# Sij_Final.net
KiCad netlist of a schematic drawn in EAGLE
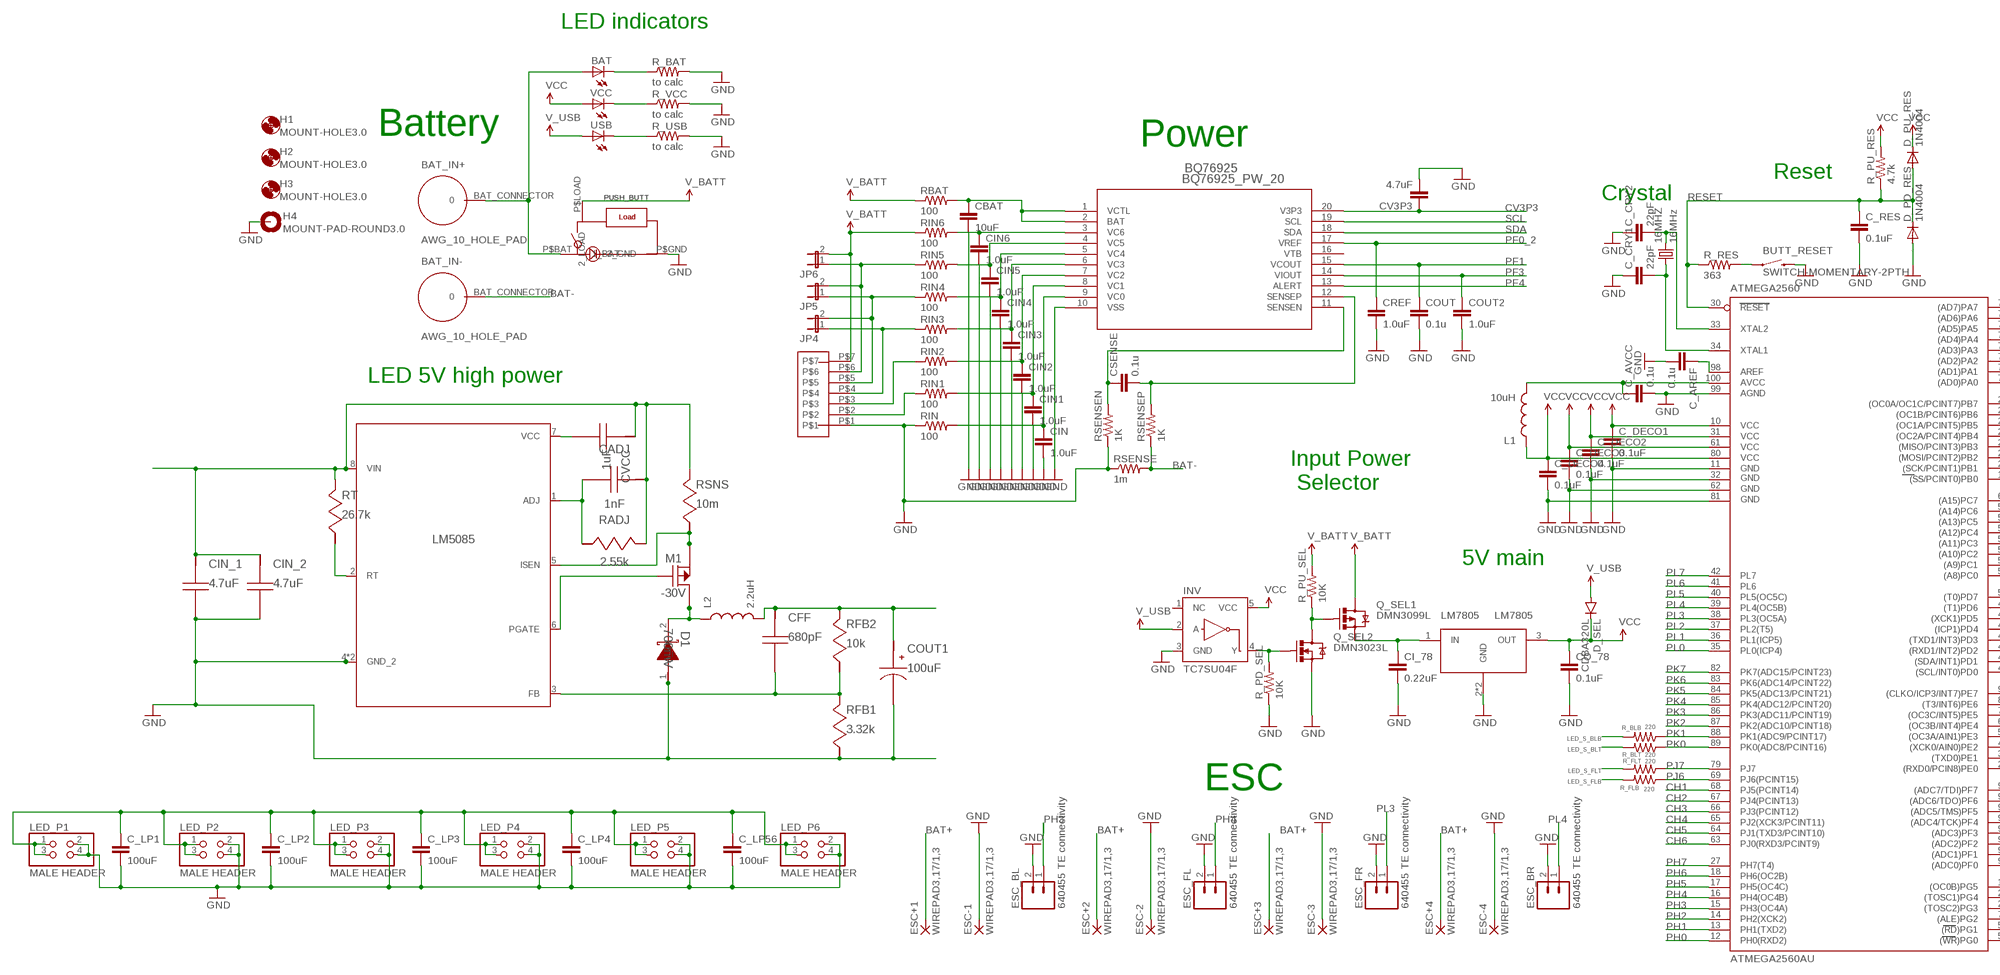
[diagram p0: schematic, sheet 1, part 1 of 2]
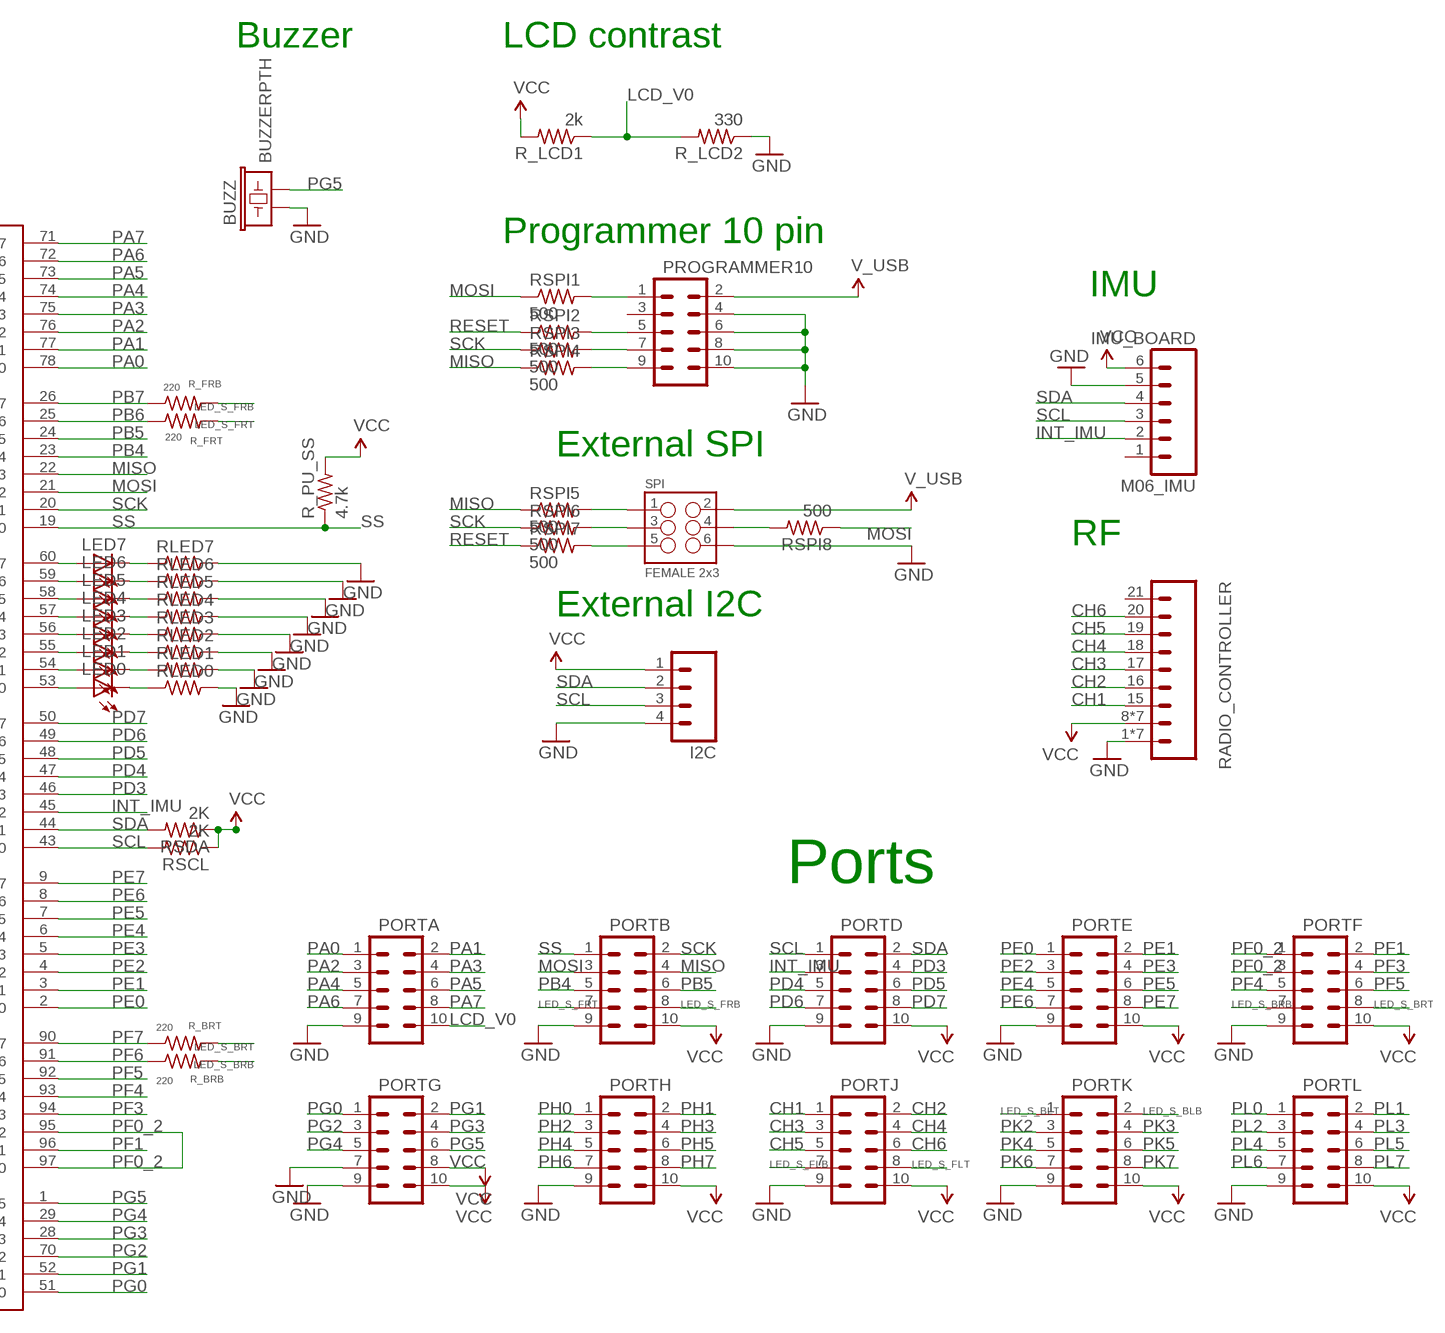
[diagram p1: schematic, sheet 1, part 2 of 2]

(export (version "E")
  (design (tool "Eeschema 10.0.6"))
  (components
    (comp (ref "16MHZ")
      (value "16MHz")
      (footprint "eagle-import:HC49US")
      (libsource (lib "eagle-import") (part "CRYSTALHC49US"))
    )
    (comp (ref "ATMEGA2560")
      (value "ATMEGA2560AU")
      (footprint "eagle-import:TQFP100")
      (libsource (lib "eagle-import") (part "ATMEGA2560AU"))
    )
    (comp (ref "BAT")
      (value "LEDCHIPLED_0805")
      (footprint "eagle-import:CHIPLED_0805")
      (libsource (lib "eagle-import") (part "LEDCHIPLED_0805"))
    )
    (comp (ref "BAT-MONIT")
      (value "7_PIN_JST-XH")
      (footprint "eagle-import:7_PIN_JST-XH")
      (libsource (lib "eagle-import") (part "7_PIN_JST-XH"))
    )
    (comp (ref "BAT_IN+")
      (value "AWG_10_HOLE_PAD")
      (footprint "eagle-import:AWG10_HOLE_PAD")
      (libsource (lib "eagle-import") (part "AWG_10_HOLE_PAD"))
    )
    (comp (ref "BAT_IN-")
      (value "AWG_10_HOLE_PAD")
      (footprint "eagle-import:AWG10_HOLE_PAD")
      (libsource (lib "eagle-import") (part "AWG_10_HOLE_PAD"))
    )
    (comp (ref "BQ76925")
      (value "BQ76925_PW_20")
      (footprint "eagle-import:PW20")
      (fields
        (field (name "GENERIC_PART_NUMBER") "BQ76925")
        (field (name "MANUFACTURER") "Texas Instruments")
        (field (name "MANUFACTURER_PART_NUMBER") "bq76925_pw_20")
      )
      (libsource (lib "eagle-import") (part "BQ76925_PW_20"))
    )
    (comp (ref "BUTT_RESET")
      (value "SWITCH-MOMENTARY-2PTH")
      (footprint "eagle-import:TACTILE-PTH")
      (libsource (lib "eagle-import") (part "SWITCH-MOMENTARY-2PTH"))
    )
    (comp (ref "BUZZ")
      (value "BUZZERPTH")
      (footprint "eagle-import:BUZZER-12MM")
      (libsource (lib "eagle-import") (part "BUZZERPTH"))
    )
    (comp (ref "CADJ")
      (value "1nF")
      (footprint "eagle-import:0201")
      (fields (field (name "MANUFACTURER_PART_NUMBER") "GRM033R71C102KA01D"))
      (libsource (lib "eagle-import") (part "GRM033R71C102KA01D"))
    )
    (comp (ref "CBAT")
      (value "10uF")
      (footprint "eagle-import:0805")
      (libsource (lib "eagle-import") (part "CAP0805"))
    )
    (comp (ref "CFF")
      (value "680pF")
      (footprint "eagle-import:0603")
      (fields (field (name "MANUFACTURER_PART_NUMBER") "GRM188R72E681KW07D"))
      (libsource (lib "eagle-import") (part "GRM188R72E681KW07D"))
    )
    (comp (ref "CIN")
      (value "1.0uF")
      (footprint "eagle-import:0603-CAP")
      (libsource (lib "eagle-import") (part "1.0UF-16V-10%(0603)"))
    )
    (comp (ref "CIN1")
      (value "1.0uF")
      (footprint "eagle-import:0603-CAP")
      (libsource (lib "eagle-import") (part "1.0UF-16V-10%(0603)"))
    )
    (comp (ref "CIN2")
      (value "1.0uF")
      (footprint "eagle-import:0603-CAP")
      (libsource (lib "eagle-import") (part "1.0UF-16V-10%(0603)"))
    )
    (comp (ref "CIN3")
      (value "1.0uF")
      (footprint "eagle-import:0603-CAP")
      (libsource (lib "eagle-import") (part "1.0UF-16V-10%(0603)"))
    )
    (comp (ref "CIN4")
      (value "1.0uF")
      (footprint "eagle-import:0603-CAP")
      (libsource (lib "eagle-import") (part "1.0UF-16V-10%(0603)"))
    )
    (comp (ref "CIN5")
      (value "1.0uF")
      (footprint "eagle-import:0603-CAP")
      (libsource (lib "eagle-import") (part "1.0UF-16V-10%(0603)"))
    )
    (comp (ref "CIN6")
      (value "1.0uF")
      (footprint "eagle-import:0603-CAP")
      (libsource (lib "eagle-import") (part "1.0UF-16V-10%(0603)"))
    )
    (comp (ref "CIN_1")
      (value "4.7uF")
      (footprint "eagle-import:0805")
      (fields (field (name "MANUFACTURER_PART_NUMBER") "GRM21BR61E475MA12L"))
      (libsource (lib "eagle-import") (part "GRM21BR61E475MA12L"))
    )
    (comp (ref "CIN_2")
      (value "4.7uF")
      (footprint "eagle-import:0805")
      (fields (field (name "MANUFACTURER_PART_NUMBER") "GRM21BR61E475MA12L"))
      (libsource (lib "eagle-import") (part "GRM21BR61E475MA12L"))
    )
    (comp (ref "CI_78")
      (value "0.22uF")
      (footprint "eagle-import:0603-CAP")
      (libsource (lib "eagle-import") (part "0.22UF-25V-10%(0603)"))
    )
    (comp (ref "COUT")
      (value "0.1u")
      (footprint "eagle-import:0603-CAP")
      (libsource (lib "eagle-import") (part "CAP0603-CAP"))
    )
    (comp (ref "COUT1")
      (value "100uF")
      (footprint "eagle-import:CAPSMT_6_A09")
      (fields (field (name "MANUFACTURER_PART_NUMBER") "6TPH100MAEA"))
      (libsource (lib "eagle-import") (part "6TPH100MAEA"))
    )
    (comp (ref "COUT2")
      (value "1.0uF")
      (footprint "eagle-import:0603-CAP")
      (libsource (lib "eagle-import") (part "1.0UF-16V-10%(0603)"))
    )
    (comp (ref "CO_78")
      (value "0.1uF")
      (footprint "eagle-import:0603-CAP")
      (libsource (lib "eagle-import") (part "0.1UF-25V-5%(0603)"))
    )
    (comp (ref "CREF")
      (value "1.0uF")
      (footprint "eagle-import:0603-CAP")
      (libsource (lib "eagle-import") (part "1.0UF-16V-10%(0603)"))
    )
    (comp (ref "CSENSE")
      (value "0.1u")
      (footprint "eagle-import:0603-CAP")
      (libsource (lib "eagle-import") (part "SparkFun-Passives_CAP0603-CAP"))
    )
    (comp (ref "CV3P3")
      (value "4.7uF")
      (footprint "eagle-import:0603-CAP")
      (libsource (lib "eagle-import") (part "4.7UF-6.3V-10%(0603)0603"))
    )
    (comp (ref "CVCC")
      (value "1uF")
      (footprint "eagle-import:0603")
      (fields (field (name "MANUFACTURER_PART_NUMBER") "GRM188R61C105KA93D"))
      (libsource (lib "eagle-import") (part "GRM188R61C105KA93D"))
    )
    (comp (ref "C_AREF")
      (value "0.1u")
      (footprint "eagle-import:0603-CAP")
      (libsource (lib "eagle-import") (part "CAP0603-CAP"))
    )
    (comp (ref "C_AVCC")
      (value "0.1u")
      (footprint "eagle-import:0603-CAP")
      (libsource (lib "eagle-import") (part "CAP0603-CAP"))
    )
    (comp (ref "C_CRY1")
      (value "22pF")
      (footprint "eagle-import:0603-CAP")
      (libsource (lib "eagle-import") (part "22PF-50V-5%(0603)"))
    )
    (comp (ref "C_CRY2")
      (value "22pF")
      (footprint "eagle-import:0603-CAP")
      (libsource (lib "eagle-import") (part "22PF-50V-5%(0603)"))
    )
    (comp (ref "C_DECO1")
      (value "0.1uF")
      (footprint "eagle-import:0603-CAP")
      (libsource (lib "eagle-import") (part "0.1UF-25V-5%(0603)"))
    )
    (comp (ref "C_DECO2")
      (value "0.1uF")
      (footprint "eagle-import:0603-CAP")
      (libsource (lib "eagle-import") (part "0.1UF-25V-5%(0603)"))
    )
    (comp (ref "C_DECO3")
      (value "0.1uF")
      (footprint "eagle-import:0603-CAP")
      (libsource (lib "eagle-import") (part "0.1UF-25V-5%(0603)"))
    )
    (comp (ref "C_DECO4")
      (value "0.1uF")
      (footprint "eagle-import:0603-CAP")
      (libsource (lib "eagle-import") (part "0.1UF-25V-5%(0603)"))
    )
    (comp (ref "C_LP1")
      (value "100uF")
      (footprint "eagle-import:1206")
      (libsource (lib "eagle-import") (part "CAP1206"))
    )
    (comp (ref "C_LP2")
      (value "100uF")
      (footprint "eagle-import:1206")
      (libsource (lib "eagle-import") (part "CAP1206"))
    )
    (comp (ref "C_LP3")
      (value "100uF")
      (footprint "eagle-import:1206")
      (libsource (lib "eagle-import") (part "CAP1206"))
    )
    (comp (ref "C_LP4")
      (value "100uF")
      (footprint "eagle-import:1206")
      (libsource (lib "eagle-import") (part "CAP1206"))
    )
    (comp (ref "C_LP56")
      (value "100uF")
      (footprint "eagle-import:1206")
      (libsource (lib "eagle-import") (part "CAP1206"))
    )
    (comp (ref "C_RES")
      (value "0.1uF")
      (footprint "eagle-import:0603-CAP")
      (libsource (lib "eagle-import") (part "0.1UF-25V-5%(0603)"))
    )
    (comp (ref "D1")
      (value "700mV")
      (footprint "eagle-import:DDPAK")
      (fields (field (name "MANUFACTURER_PART_NUMBER") "MBRB745PBF"))
      (libsource (lib "eagle-import") (part "MBRB745PBF"))
    )
    (comp (ref "D_PD_RES")
      (value "1N4004")
      (footprint "eagle-import:DO41-10")
      (libsource (lib "eagle-import") (part "1N4004"))
    )
    (comp (ref "D_PU_RES")
      (value "1N4004")
      (footprint "eagle-import:DO41-10")
      (libsource (lib "eagle-import") (part "1N4004"))
    )
    (comp (ref "D_SEL")
      (value "CDBA320L")
      (footprint "eagle-import:SMA-DIODE_ALT")
      (libsource (lib "eagle-import") (part "DIODESMA-ALT"))
    )
    (comp (ref "ESC+1")
      (value "WIREPAD3,17/1,3")
      (footprint "eagle-import:3,17_1,3")
      (libsource (lib "eagle-import") (part "WIREPAD3,17/1,3"))
    )
    (comp (ref "ESC+2")
      (value "WIREPAD3,17/1,3")
      (footprint "eagle-import:3,17_1,3")
      (libsource (lib "eagle-import") (part "WIREPAD3,17/1,3"))
    )
    (comp (ref "ESC+3")
      (value "WIREPAD3,17/1,3")
      (footprint "eagle-import:3,17_1,3")
      (libsource (lib "eagle-import") (part "WIREPAD3,17/1,3"))
    )
    (comp (ref "ESC+4")
      (value "WIREPAD3,17/1,3")
      (footprint "eagle-import:3,17_1,3")
      (libsource (lib "eagle-import") (part "WIREPAD3,17/1,3"))
    )
    (comp (ref "ESC-1")
      (value "WIREPAD3,17/1,3")
      (footprint "eagle-import:3,17_1,3")
      (libsource (lib "eagle-import") (part "WIREPAD3,17/1,3"))
    )
    (comp (ref "ESC-2")
      (value "WIREPAD3,17/1,3")
      (footprint "eagle-import:3,17_1,3")
      (libsource (lib "eagle-import") (part "WIREPAD3,17/1,3"))
    )
    (comp (ref "ESC-3")
      (value "WIREPAD3,17/1,3")
      (footprint "eagle-import:3,17_1,3")
      (libsource (lib "eagle-import") (part "WIREPAD3,17/1,3"))
    )
    (comp (ref "ESC-4")
      (value "WIREPAD3,17/1,3")
      (footprint "eagle-import:3,17_1,3")
      (libsource (lib "eagle-import") (part "WIREPAD3,17/1,3"))
    )
    (comp (ref "ESC_BL")
      (value "640455 TE connectivity")
      (footprint "eagle-import:1X02")
      (libsource (lib "eagle-import") (part "M02PTH"))
    )
    (comp (ref "ESC_BR")
      (value "640455 TE connectivity")
      (footprint "eagle-import:1X02")
      (libsource (lib "eagle-import") (part "M02PTH"))
    )
    (comp (ref "ESC_FL")
      (value "640455 TE connectivity")
      (footprint "eagle-import:1X02")
      (libsource (lib "eagle-import") (part "M02PTH"))
    )
    (comp (ref "ESC_FR")
      (value "640455 TE connectivity")
      (footprint "eagle-import:1X02")
      (libsource (lib "eagle-import") (part "M02PTH"))
    )
    (comp (ref "H1")
      (value "MOUNT-HOLE3.0")
      (footprint "eagle-import:3,0")
      (libsource (lib "eagle-import") (part "MOUNT-HOLE3.0"))
    )
    (comp (ref "H2")
      (value "MOUNT-HOLE3.0")
      (footprint "eagle-import:3,0")
      (libsource (lib "eagle-import") (part "MOUNT-HOLE3.0"))
    )
    (comp (ref "H3")
      (value "MOUNT-HOLE3.0")
      (footprint "eagle-import:3,0")
      (libsource (lib "eagle-import") (part "MOUNT-HOLE3.0"))
    )
    (comp (ref "H4")
      (value "MOUNT-PAD-ROUND3.0")
      (footprint "eagle-import:3,0-PAD")
      (libsource (lib "eagle-import") (part "MOUNT-PAD-ROUND3.0"))
    )
    (comp (ref "I2C")
      (value "M041X04_NO_SILK")
      (footprint "eagle-import:1X04_NO_SILK")
      (libsource (lib "eagle-import") (part "M041X04_NO_SILK"))
    )
    (comp (ref "IMU_BOARD")
      (value "M06_IMU")
      (footprint "eagle-import:1X06_LONGPADS")
      (libsource (lib "eagle-import") (part "M06_IMU"))
    )
    (comp (ref "INV")
      (value "TC7SU04F")
      (footprint "eagle-import:SOT23-5")
      (libsource (lib "eagle-import") (part "INVERTER_SOT23-5"))
    )
    (comp (ref "JP4")
      (value "JUMPER-2PTH")
      (footprint "eagle-import:1X02")
      (libsource (lib "eagle-import") (part "JUMPER-2PTH"))
    )
    (comp (ref "JP5")
      (value "JUMPER-2PTH")
      (footprint "eagle-import:1X02")
      (libsource (lib "eagle-import") (part "JUMPER-2PTH"))
    )
    (comp (ref "JP6")
      (value "JUMPER-2PTH")
      (footprint "eagle-import:1X02")
      (libsource (lib "eagle-import") (part "JUMPER-2PTH"))
    )
    (comp (ref "L1")
      (value "10uH")
      (footprint "eagle-import:0805")
      (libsource (lib "eagle-import") (part "INDUCTOR0805"))
    )
    (comp (ref "L2")
      (value "2.2uH")
      (footprint "eagle-import:MGV0605")
      (libsource (lib "eagle-import") (part "IND_MGV0605"))
    )
    (comp (ref "LED0")
      (value "LEDCHIPLED_0805")
      (footprint "eagle-import:CHIPLED_0805")
      (libsource (lib "eagle-import") (part "LEDCHIPLED_0805"))
    )
    (comp (ref "LED1")
      (value "LEDCHIPLED_0805")
      (footprint "eagle-import:CHIPLED_0805")
      (libsource (lib "eagle-import") (part "LEDCHIPLED_0805"))
    )
    (comp (ref "LED2")
      (value "LEDCHIPLED_0805")
      (footprint "eagle-import:CHIPLED_0805")
      (libsource (lib "eagle-import") (part "LEDCHIPLED_0805"))
    )
    (comp (ref "LED3")
      (value "LEDCHIPLED_0805")
      (footprint "eagle-import:CHIPLED_0805")
      (libsource (lib "eagle-import") (part "LEDCHIPLED_0805"))
    )
    (comp (ref "LED4")
      (value "LEDCHIPLED_0805")
      (footprint "eagle-import:CHIPLED_0805")
      (libsource (lib "eagle-import") (part "LEDCHIPLED_0805"))
    )
    (comp (ref "LED5")
      (value "LEDCHIPLED_0805")
      (footprint "eagle-import:CHIPLED_0805")
      (libsource (lib "eagle-import") (part "LEDCHIPLED_0805"))
    )
    (comp (ref "LED6")
      (value "LEDCHIPLED_0805")
      (footprint "eagle-import:CHIPLED_0805")
      (libsource (lib "eagle-import") (part "LEDCHIPLED_0805"))
    )
    (comp (ref "LED7")
      (value "LEDCHIPLED_0805")
      (footprint "eagle-import:CHIPLED_0805")
      (libsource (lib "eagle-import") (part "LEDCHIPLED_0805"))
    )
    (comp (ref "LED_P1")
      (value "MALE HEADER")
      (footprint "eagle-import:2X02")
      (libsource (lib "eagle-import") (part "PINHD-2X2"))
    )
    (comp (ref "LED_P2")
      (value "MALE HEADER")
      (footprint "eagle-import:2X02")
      (libsource (lib "eagle-import") (part "PINHD-2X2"))
    )
    (comp (ref "LED_P3")
      (value "MALE HEADER")
      (footprint "eagle-import:2X02")
      (libsource (lib "eagle-import") (part "PINHD-2X2"))
    )
    (comp (ref "LED_P4")
      (value "MALE HEADER")
      (footprint "eagle-import:2X02")
      (libsource (lib "eagle-import") (part "PINHD-2X2"))
    )
    (comp (ref "LED_P5")
      (value "MALE HEADER")
      (footprint "eagle-import:2X02")
      (libsource (lib "eagle-import") (part "PINHD-2X2"))
    )
    (comp (ref "LED_P6")
      (value "MALE HEADER")
      (footprint "eagle-import:2X02")
      (libsource (lib "eagle-import") (part "PINHD-2X2"))
    )
    (comp (ref "LM5085")
      (value "LM5085MY/NOPB")
      (footprint "eagle-import:MUY08A")
      (libsource (lib "eagle-import") (part "LM5085MY/NOPB"))
    )
    (comp (ref "LM7805")
      (value "LM7805")
      (footprint "eagle-import:KTT3")
      (libsource (lib "eagle-import") (part "LM7805"))
    )
    (comp (ref "M1")
      (value "-30V")
      (footprint "eagle-import:POWERPAK_SO-8")
      (fields (field (name "MANUFACTURER_PART_NUMBER") "Si7149DP"))
      (libsource (lib "eagle-import") (part "SI7149DP"))
    )
    (comp (ref "PORTA")
      (value "M05X2PTH")
      (footprint "eagle-import:AVR_ICSP")
      (libsource (lib "eagle-import") (part "M05X2PTH"))
    )
    (comp (ref "PORTB")
      (value "M05X2PTH")
      (footprint "eagle-import:AVR_ICSP")
      (libsource (lib "eagle-import") (part "M05X2PTH"))
    )
    (comp (ref "PORTD")
      (value "M05X2PTH")
      (footprint "eagle-import:AVR_ICSP")
      (libsource (lib "eagle-import") (part "M05X2PTH"))
    )
    (comp (ref "PORTE")
      (value "M05X2PTH")
      (footprint "eagle-import:AVR_ICSP")
      (libsource (lib "eagle-import") (part "M05X2PTH"))
    )
    (comp (ref "PORTF")
      (value "M05X2PTH")
      (footprint "eagle-import:AVR_ICSP")
      (libsource (lib "eagle-import") (part "M05X2PTH"))
    )
    (comp (ref "PORTG")
      (value "M05X2PTH")
      (footprint "eagle-import:AVR_ICSP")
      (libsource (lib "eagle-import") (part "M05X2PTH"))
    )
    (comp (ref "PORTH")
      (value "M05X2PTH")
      (footprint "eagle-import:AVR_ICSP")
      (libsource (lib "eagle-import") (part "M05X2PTH"))
    )
    (comp (ref "PORTJ")
      (value "M05X2PTH")
      (footprint "eagle-import:AVR_ICSP")
      (libsource (lib "eagle-import") (part "M05X2PTH"))
    )
    (comp (ref "PORTK")
      (value "M05X2PTH")
      (footprint "eagle-import:AVR_ICSP")
      (libsource (lib "eagle-import") (part "M05X2PTH"))
    )
    (comp (ref "PORTL")
      (value "M05X2PTH")
      (footprint "eagle-import:AVR_ICSP")
      (libsource (lib "eagle-import") (part "M05X2PTH"))
    )
    (comp (ref "PROGRAMMER10")
      (value "M05X2PTH")
      (footprint "eagle-import:AVR_ICSP")
      (libsource (lib "eagle-import") (part "M05X2PTH"))
    )
    (comp (ref "PUSH_BUTT")
      (value "PUSH_BUTTON")
      (footprint "eagle-import:PUSH_BUTTON")
      (libsource (lib "eagle-import") (part "PUSH_BUTTON"))
    )
    (comp (ref "Q_SEL1")
      (value "DMN3099L")
      (footprint "eagle-import:SOT23-3")
      (libsource (lib "eagle-import") (part "MOSFET-PCHANNEL"))
    )
    (comp (ref "Q_SEL2")
      (value "DMN3023L")
      (footprint "eagle-import:SOT23-3")
      (libsource (lib "eagle-import") (part "MOSFET-NCHANNELAO3404A"))
    )
    (comp (ref "RADIO_CONTROLLER")
      (value "RF_CONTROL_3X7_CON")
      (footprint "eagle-import:3X07")
      (libsource (lib "eagle-import") (part "RF_CONTROL_3X7_CON"))
    )
    (comp (ref "RADJ")
      (value "2.55k")
      (footprint "eagle-import:0603")
      (libsource (lib "eagle-import") (part "CRCW04022K55FKED"))
    )
    (comp (ref "RBAT")
      (value "100")
      (footprint "eagle-import:R0603")
      (libsource (lib "eagle-import") (part "R-US_R0603"))
    )
    (comp (ref "RFB1")
      (value "3.32k")
      (footprint "eagle-import:0603")
      (libsource (lib "eagle-import") (part "CRCW04023K32FKED"))
    )
    (comp (ref "RFB2")
      (value "10k")
      (footprint "eagle-import:0603")
      (libsource (lib "eagle-import") (part "CRCW040210K0FKED"))
    )
    (comp (ref "RIN")
      (value "100")
      (footprint "eagle-import:R0603")
      (libsource (lib "eagle-import") (part "R-US_R0603"))
    )
    (comp (ref "RIN1")
      (value "100")
      (footprint "eagle-import:R0603")
      (libsource (lib "eagle-import") (part "R-US_R0603"))
    )
    (comp (ref "RIN2")
      (value "100")
      (footprint "eagle-import:R0603")
      (libsource (lib "eagle-import") (part "R-US_R0603"))
    )
    (comp (ref "RIN3")
      (value "100")
      (footprint "eagle-import:R0603")
      (libsource (lib "eagle-import") (part "R-US_R0603"))
    )
    (comp (ref "RIN4")
      (value "100")
      (footprint "eagle-import:R0603")
      (libsource (lib "eagle-import") (part "R-US_R0603"))
    )
    (comp (ref "RIN5")
      (value "100")
      (footprint "eagle-import:R0603")
      (libsource (lib "eagle-import") (part "R-US_R0603"))
    )
    (comp (ref "RIN6")
      (value "100")
      (footprint "eagle-import:R0603")
      (libsource (lib "eagle-import") (part "R-US_R0603"))
    )
    (comp (ref "RLED0")
      (value "R-US_R0603")
      (footprint "eagle-import:R0603")
      (libsource (lib "eagle-import") (part "R-US_R0603"))
    )
    (comp (ref "RLED1")
      (value "R-US_R0603")
      (footprint "eagle-import:R0603")
      (libsource (lib "eagle-import") (part "R-US_R0603"))
    )
    (comp (ref "RLED2")
      (value "R-US_R0603")
      (footprint "eagle-import:R0603")
      (libsource (lib "eagle-import") (part "R-US_R0603"))
    )
    (comp (ref "RLED3")
      (value "R-US_R0603")
      (footprint "eagle-import:R0603")
      (libsource (lib "eagle-import") (part "R-US_R0603"))
    )
    (comp (ref "RLED4")
      (value "R-US_R0603")
      (footprint "eagle-import:R0603")
      (libsource (lib "eagle-import") (part "R-US_R0603"))
    )
    (comp (ref "RLED5")
      (value "R-US_R0603")
      (footprint "eagle-import:R0603")
      (libsource (lib "eagle-import") (part "R-US_R0603"))
    )
    (comp (ref "RLED6")
      (value "R-US_R0603")
      (footprint "eagle-import:R0603")
      (libsource (lib "eagle-import") (part "R-US_R0603"))
    )
    (comp (ref "RLED7")
      (value "R-US_R0603")
      (footprint "eagle-import:R0603")
      (libsource (lib "eagle-import") (part "R-US_R0603"))
    )
    (comp (ref "RSCL")
      (value "2K")
      (footprint "eagle-import:R0603")
      (libsource (lib "eagle-import") (part "R-US_R0603"))
    )
    (comp (ref "RSDA")
      (value "2K")
      (footprint "eagle-import:R0603")
      (libsource (lib "eagle-import") (part "R-US_R0603"))
    )
    (comp (ref "RSENSE")
      (value "1m")
      (footprint "eagle-import:R1206")
      (libsource (lib "eagle-import") (part "R-US_R1206"))
    )
    (comp (ref "RSENSEN")
      (value "1K")
      (footprint "eagle-import:R0603")
      (libsource (lib "eagle-import") (part "R-US_R0603"))
    )
    (comp (ref "RSENSEP")
      (value "1K")
      (footprint "eagle-import:R0603")
      (libsource (lib "eagle-import") (part "R-US_R0603"))
    )
    (comp (ref "RSNS")
      (value "10m")
      (footprint "eagle-import:1206")
      (fields
        (field (name "MANUFACTURER_PART_NUMBER") "CSR1206FK10L0")
        (field (name "POWER") "0.5")
        (field (name "TOLERANCE") "1.0")
      )
      (libsource (lib "eagle-import") (part "CSR1206FK10L0"))
    )
    (comp (ref "RSPI1")
      (value "500")
      (footprint "eagle-import:R0603")
      (libsource (lib "eagle-import") (part "R-US_R0603"))
    )
    (comp (ref "RSPI2")
      (value "500")
      (footprint "eagle-import:R0603")
      (libsource (lib "eagle-import") (part "R-US_R0603"))
    )
    (comp (ref "RSPI3")
      (value "500")
      (footprint "eagle-import:R0603")
      (libsource (lib "eagle-import") (part "R-US_R0603"))
    )
    (comp (ref "RSPI4")
      (value "500")
      (footprint "eagle-import:R0603")
      (libsource (lib "eagle-import") (part "R-US_R0603"))
    )
    (comp (ref "RSPI5")
      (value "500")
      (footprint "eagle-import:R0603")
      (libsource (lib "eagle-import") (part "R-US_R0603"))
    )
    (comp (ref "RSPI6")
      (value "500")
      (footprint "eagle-import:R0603")
      (libsource (lib "eagle-import") (part "R-US_R0603"))
    )
    (comp (ref "RSPI7")
      (value "500")
      (footprint "eagle-import:R0603")
      (libsource (lib "eagle-import") (part "R-US_R0603"))
    )
    (comp (ref "RSPI8")
      (value "500")
      (footprint "eagle-import:R0603")
      (libsource (lib "eagle-import") (part "R-US_R0603"))
    )
    (comp (ref "RT")
      (value "26.7k")
      (footprint "eagle-import:0603")
      (libsource (lib "eagle-import") (part "CRCW040226K7FKED"))
    )
    (comp (ref "R_BAT")
      (value "to calc")
      (footprint "eagle-import:R0603")
      (libsource (lib "eagle-import") (part "R-US_R0603"))
    )
    (comp (ref "R_BLB")
      (value "220")
      (footprint "eagle-import:R0603")
      (libsource (lib "eagle-import") (part "R-US_R0603"))
    )
    (comp (ref "R_BLT")
      (value "220")
      (footprint "eagle-import:R0603")
      (libsource (lib "eagle-import") (part "R-US_R0603"))
    )
    (comp (ref "R_BRB")
      (value "220")
      (footprint "eagle-import:R0603")
      (libsource (lib "eagle-import") (part "R-US_R0603"))
    )
    (comp (ref "R_BRT")
      (value "220")
      (footprint "eagle-import:R0603")
      (libsource (lib "eagle-import") (part "R-US_R0603"))
    )
    (comp (ref "R_FLB")
      (value "220")
      (footprint "eagle-import:R0603")
      (libsource (lib "eagle-import") (part "R-US_R0603"))
    )
    (comp (ref "R_FLT")
      (value "220")
      (footprint "eagle-import:R0603")
      (libsource (lib "eagle-import") (part "R-US_R0603"))
    )
    (comp (ref "R_FRB")
      (value "220")
      (footprint "eagle-import:R0603")
      (libsource (lib "eagle-import") (part "R-US_R0603"))
    )
    (comp (ref "R_FRT")
      (value "220")
      (footprint "eagle-import:R0603")
      (libsource (lib "eagle-import") (part "R-US_R0603"))
    )
    (comp (ref "R_LCD1")
      (value "2k")
      (footprint "eagle-import:R0603")
      (libsource (lib "eagle-import") (part "R-US_R0603"))
    )
    (comp (ref "R_LCD2")
      (value "330")
      (footprint "eagle-import:R0603")
      (libsource (lib "eagle-import") (part "R-US_R0603"))
    )
    (comp (ref "R_PD_SEL")
      (value "10K")
      (footprint "eagle-import:R0603")
      (libsource (lib "eagle-import") (part "R-US_R0603"))
    )
    (comp (ref "R_PU_RES")
      (value "4.7k")
      (footprint "eagle-import:R0603")
      (libsource (lib "eagle-import") (part "R-US_R0603"))
    )
    (comp (ref "R_PU_SEL")
      (value "10K")
      (footprint "eagle-import:R0603")
      (libsource (lib "eagle-import") (part "R-US_R0603"))
    )
    (comp (ref "R_PU_SS")
      (value "4.7k")
      (footprint "eagle-import:R0603")
      (libsource (lib "eagle-import") (part "R-US_R0603"))
    )
    (comp (ref "R_RES")
      (value "363")
      (footprint "eagle-import:R0603")
      (libsource (lib "eagle-import") (part "R-US_R0603"))
    )
    (comp (ref "R_USB")
      (value "to calc")
      (footprint "eagle-import:R0603")
      (libsource (lib "eagle-import") (part "R-US_R0603"))
    )
    (comp (ref "R_VCC")
      (value "to calc")
      (footprint "eagle-import:R0603")
      (libsource (lib "eagle-import") (part "R-US_R0603"))
    )
    (comp (ref "SPI")
      (value "FEMALE 2x3")
      (footprint "eagle-import:2X3")
      (libsource (lib "eagle-import") (part "M03X2FEMALE"))
    )
    (comp (ref "USB")
      (value "LEDCHIPLED_0805")
      (footprint "eagle-import:CHIPLED_0805")
      (libsource (lib "eagle-import") (part "LEDCHIPLED_0805"))
    )
    (comp (ref "VCC")
      (value "LEDCHIPLED_0805")
      (footprint "eagle-import:CHIPLED_0805")
      (libsource (lib "eagle-import") (part "LEDCHIPLED_0805"))
    )
  )
  (nets
    (net (code "1") (name "/BAT+") (class "Default")
      (node (ref "BAT") (pin "A") (pinfunction "A_A") (pintype "passive"))
      (node (ref "BAT_IN+") (pin "BAT_CONNECTOR") (pinfunction "0_BAT_CONNECTOR") (pintype "bidirectional"))
      (node (ref "ESC+1") (pin "1") (pinfunction "P_1") (pintype "passive"))
      (node (ref "ESC+2") (pin "1") (pinfunction "P_1") (pintype "passive"))
      (node (ref "ESC+3") (pin "1") (pinfunction "P_1") (pintype "passive"))
      (node (ref "ESC+4") (pin "1") (pinfunction "P_1") (pintype "passive"))
      (node (ref "PUSH_BUTT") (pin "P$BAT") (pinfunction "1_BAT_P$BAT") (pintype "bidirectional"))
    )
    (net (code "2") (name "/BAT-") (class "Default")
      (node (ref "BAT_IN-") (pin "BAT_CONNECTOR") (pinfunction "0_BAT_CONNECTOR") (pintype "bidirectional"))
      (node (ref "RSENSE") (pin "2") (pinfunction "2_2") (pintype "passive"))
      (node (ref "RSENSEP") (pin "1") (pinfunction "1_1") (pintype "passive"))
    )
    (net (code "3") (name "/CH1") (class "Default")
      (node (ref "ATMEGA2560") (pin "68") (pinfunction "PJ5(PCINT14)_68") (pintype "bidirectional"))
      (node (ref "PORTJ") (pin "1") (pinfunction "1_1") (pintype "passive"))
      (node (ref "RADIO_CONTROLLER") (pin "15") (pinfunction "1_15") (pintype "bidirectional"))
    )
    (net (code "4") (name "/CH2") (class "Default")
      (node (ref "ATMEGA2560") (pin "67") (pinfunction "PJ4(PCINT13)_67") (pintype "bidirectional"))
      (node (ref "PORTJ") (pin "2") (pinfunction "2_2") (pintype "passive"))
      (node (ref "RADIO_CONTROLLER") (pin "16") (pinfunction "2_16") (pintype "bidirectional"))
    )
    (net (code "5") (name "/CH3") (class "Default")
      (node (ref "ATMEGA2560") (pin "66") (pinfunction "PJ3(PCINT12)_66") (pintype "bidirectional"))
      (node (ref "PORTJ") (pin "3") (pinfunction "3_3") (pintype "passive"))
      (node (ref "RADIO_CONTROLLER") (pin "17") (pinfunction "3_17") (pintype "bidirectional"))
    )
    (net (code "6") (name "/CH4") (class "Default")
      (node (ref "ATMEGA2560") (pin "65") (pinfunction "PJ2(XCK3/PCINT11)_65") (pintype "bidirectional"))
      (node (ref "PORTJ") (pin "4") (pinfunction "4_4") (pintype "passive"))
      (node (ref "RADIO_CONTROLLER") (pin "18") (pinfunction "4_18") (pintype "bidirectional"))
    )
    (net (code "7") (name "/CH5") (class "Default")
      (node (ref "ATMEGA2560") (pin "64") (pinfunction "PJ1(TXD3/PCINT10)_64") (pintype "bidirectional"))
      (node (ref "PORTJ") (pin "5") (pinfunction "5_5") (pintype "passive"))
      (node (ref "RADIO_CONTROLLER") (pin "19") (pinfunction "5_19") (pintype "bidirectional"))
    )
    (net (code "8") (name "/CH6") (class "Default")
      (node (ref "ATMEGA2560") (pin "63") (pinfunction "PJ0(RXD3/PCINT9)_63") (pintype "bidirectional"))
      (node (ref "PORTJ") (pin "6") (pinfunction "6_6") (pintype "passive"))
      (node (ref "RADIO_CONTROLLER") (pin "20") (pinfunction "6_20") (pintype "bidirectional"))
    )
    (net (code "9") (name "/CV3P3") (class "Default")
      (node (ref "BQ76925") (pin "20") (pinfunction "V3P3_20") (pintype "output"))
      (node (ref "CV3P3") (pin "1") (pinfunction "1_1") (pintype "passive"))
    )
    (net (code "10") (name "/INT_IMU") (class "Default")
      (node (ref "ATMEGA2560") (pin "45") (pinfunction "(RXD1/INT2)PD2_45") (pintype "bidirectional"))
      (node (ref "IMU_BOARD") (pin "2") (pinfunction "2_2") (pintype "passive"))
      (node (ref "PORTD") (pin "3") (pinfunction "3_3") (pintype "passive"))
    )
    (net (code "11") (name "/LCD_V0") (class "Default")
      (node (ref "PORTA") (pin "10") (pinfunction "10_10") (pintype "passive"))
      (node (ref "R_LCD1") (pin "1") (pinfunction "1_1") (pintype "passive"))
      (node (ref "R_LCD2") (pin "2") (pinfunction "2_2") (pintype "passive"))
    )
    (net (code "12") (name "/LED_S_BLB") (class "Default")
      (node (ref "PORTK") (pin "2") (pinfunction "2_2") (pintype "passive"))
      (node (ref "R_BLB") (pin "2") (pinfunction "2_2") (pintype "passive"))
    )
    (net (code "13") (name "/LED_S_BLT") (class "Default")
      (node (ref "PORTK") (pin "1") (pinfunction "1_1") (pintype "passive"))
      (node (ref "R_BLT") (pin "2") (pinfunction "2_2") (pintype "passive"))
    )
    (net (code "14") (name "/LED_S_BRB") (class "Default")
      (node (ref "PORTF") (pin "7") (pinfunction "7_7") (pintype "passive"))
      (node (ref "R_BRB") (pin "2") (pinfunction "2_2") (pintype "passive"))
    )
    (net (code "15") (name "/LED_S_BRT") (class "Default")
      (node (ref "PORTF") (pin "8") (pinfunction "8_8") (pintype "passive"))
      (node (ref "R_BRT") (pin "2") (pinfunction "2_2") (pintype "passive"))
    )
    (net (code "16") (name "/LED_S_FLB") (class "Default")
      (node (ref "PORTJ") (pin "7") (pinfunction "7_7") (pintype "passive"))
      (node (ref "R_FLB") (pin "2") (pinfunction "2_2") (pintype "passive"))
    )
    (net (code "17") (name "/LED_S_FLT") (class "Default")
      (node (ref "PORTJ") (pin "8") (pinfunction "8_8") (pintype "passive"))
      (node (ref "R_FLT") (pin "2") (pinfunction "2_2") (pintype "passive"))
    )
    (net (code "18") (name "/LED_S_FRB") (class "Default")
      (node (ref "PORTB") (pin "8") (pinfunction "8_8") (pintype "passive"))
      (node (ref "R_FRB") (pin "2") (pinfunction "2_2") (pintype "passive"))
    )
    (net (code "19") (name "/LED_S_FRT") (class "Default")
      (node (ref "PORTB") (pin "7") (pinfunction "7_7") (pintype "passive"))
      (node (ref "R_FRT") (pin "2") (pinfunction "2_2") (pintype "passive"))
    )
    (net (code "20") (name "/MISO") (class "Default")
      (node (ref "ATMEGA2560") (pin "22") (pinfunction "(MISO/PCINT3)PB3_22") (pintype "bidirectional"))
      (node (ref "PORTB") (pin "4") (pinfunction "4_4") (pintype "passive"))
      (node (ref "RSPI4") (pin "1") (pinfunction "1_1") (pintype "passive"))
      (node (ref "RSPI5") (pin "1") (pinfunction "1_1") (pintype "passive"))
    )
    (net (code "21") (name "/MOSI") (class "Default")
      (node (ref "ATMEGA2560") (pin "21") (pinfunction "(MOSI/PCINT2)PB2_21") (pintype "bidirectional"))
      (node (ref "PORTB") (pin "3") (pinfunction "3_3") (pintype "passive"))
      (node (ref "RSPI1") (pin "1") (pinfunction "1_1") (pintype "passive"))
      (node (ref "RSPI8") (pin "1") (pinfunction "1_1") (pintype "passive"))
    )
    (net (code "22") (name "/PA0") (class "Default")
      (node (ref "ATMEGA2560") (pin "78") (pinfunction "(AD0)PA0_78") (pintype "bidirectional"))
      (node (ref "PORTA") (pin "1") (pinfunction "1_1") (pintype "passive"))
    )
    (net (code "23") (name "/PA1") (class "Default")
      (node (ref "ATMEGA2560") (pin "77") (pinfunction "(AD1)PA1_77") (pintype "bidirectional"))
      (node (ref "PORTA") (pin "2") (pinfunction "2_2") (pintype "passive"))
    )
    (net (code "24") (name "/PA2") (class "Default")
      (node (ref "ATMEGA2560") (pin "76") (pinfunction "(AD2)PA2_76") (pintype "bidirectional"))
      (node (ref "PORTA") (pin "3") (pinfunction "3_3") (pintype "passive"))
    )
    (net (code "25") (name "/PA3") (class "Default")
      (node (ref "ATMEGA2560") (pin "75") (pinfunction "(AD3)PA3_75") (pintype "bidirectional"))
      (node (ref "PORTA") (pin "4") (pinfunction "4_4") (pintype "passive"))
    )
    (net (code "26") (name "/PA4") (class "Default")
      (node (ref "ATMEGA2560") (pin "74") (pinfunction "(AD4)PA4_74") (pintype "bidirectional"))
      (node (ref "PORTA") (pin "5") (pinfunction "5_5") (pintype "passive"))
    )
    (net (code "27") (name "/PA5") (class "Default")
      (node (ref "ATMEGA2560") (pin "73") (pinfunction "(AD5)PA5_73") (pintype "bidirectional"))
      (node (ref "PORTA") (pin "6") (pinfunction "6_6") (pintype "passive"))
    )
    (net (code "28") (name "/PA6") (class "Default")
      (node (ref "ATMEGA2560") (pin "72") (pinfunction "(AD6)PA6_72") (pintype "bidirectional"))
      (node (ref "PORTA") (pin "7") (pinfunction "7_7") (pintype "passive"))
    )
    (net (code "29") (name "/PA7") (class "Default")
      (node (ref "ATMEGA2560") (pin "71") (pinfunction "(AD7)PA7_71") (pintype "bidirectional"))
      (node (ref "PORTA") (pin "8") (pinfunction "8_8") (pintype "passive"))
    )
    (net (code "30") (name "/PB4") (class "Default")
      (node (ref "ATMEGA2560") (pin "23") (pinfunction "(OC2A/PCINT4)PB4_23") (pintype "bidirectional"))
      (node (ref "PORTB") (pin "5") (pinfunction "5_5") (pintype "passive"))
    )
    (net (code "31") (name "/PB5") (class "Default")
      (node (ref "ATMEGA2560") (pin "24") (pinfunction "(OC1A/PCINT5)PB5_24") (pintype "bidirectional"))
      (node (ref "PORTB") (pin "6") (pinfunction "6_6") (pintype "passive"))
    )
    (net (code "32") (name "/PB6") (class "Default")
      (node (ref "ATMEGA2560") (pin "25") (pinfunction "(OC1B/PCINT6)PB6_25") (pintype "bidirectional"))
      (node (ref "R_FRT") (pin "1") (pinfunction "1_1") (pintype "passive"))
    )
    (net (code "33") (name "/PB7") (class "Default")
      (node (ref "ATMEGA2560") (pin "26") (pinfunction "(OC0A/OC1C/PCINT7)PB7_26") (pintype "bidirectional"))
      (node (ref "R_FRB") (pin "1") (pinfunction "1_1") (pintype "passive"))
    )
    (net (code "34") (name "/PD3") (class "Default")
      (node (ref "ATMEGA2560") (pin "46") (pinfunction "(TXD1/INT3)PD3_46") (pintype "bidirectional"))
      (node (ref "PORTD") (pin "4") (pinfunction "4_4") (pintype "passive"))
    )
    (net (code "35") (name "/PD4") (class "Default")
      (node (ref "ATMEGA2560") (pin "47") (pinfunction "(ICP1)PD4_47") (pintype "bidirectional"))
      (node (ref "PORTD") (pin "5") (pinfunction "5_5") (pintype "passive"))
    )
    (net (code "36") (name "/PD5") (class "Default")
      (node (ref "ATMEGA2560") (pin "48") (pinfunction "(XCK1)PD5_48") (pintype "bidirectional"))
      (node (ref "PORTD") (pin "6") (pinfunction "6_6") (pintype "passive"))
    )
    (net (code "37") (name "/PD6") (class "Default")
      (node (ref "ATMEGA2560") (pin "49") (pinfunction "(T1)PD6_49") (pintype "bidirectional"))
      (node (ref "PORTD") (pin "7") (pinfunction "7_7") (pintype "passive"))
    )
    (net (code "38") (name "/PD7") (class "Default")
      (node (ref "ATMEGA2560") (pin "50") (pinfunction "(T0)PD7_50") (pintype "bidirectional"))
      (node (ref "PORTD") (pin "8") (pinfunction "8_8") (pintype "passive"))
    )
    (net (code "39") (name "/PE0") (class "Default")
      (node (ref "ATMEGA2560") (pin "2") (pinfunction "(RXD0/PCIN8)PE0_2") (pintype "bidirectional"))
      (node (ref "PORTE") (pin "1") (pinfunction "1_1") (pintype "passive"))
    )
    (net (code "40") (name "/PE1") (class "Default")
      (node (ref "ATMEGA2560") (pin "3") (pinfunction "(TXD0)PE1_3") (pintype "bidirectional"))
      (node (ref "PORTE") (pin "2") (pinfunction "2_2") (pintype "passive"))
    )
    (net (code "41") (name "/PE2") (class "Default")
      (node (ref "ATMEGA2560") (pin "4") (pinfunction "(XCK0/AIN0)PE2_4") (pintype "bidirectional"))
      (node (ref "PORTE") (pin "3") (pinfunction "3_3") (pintype "passive"))
    )
    (net (code "42") (name "/PE3") (class "Default")
      (node (ref "ATMEGA2560") (pin "5") (pinfunction "(OC3A/AIN1)PE3_5") (pintype "bidirectional"))
      (node (ref "PORTE") (pin "4") (pinfunction "4_4") (pintype "passive"))
    )
    (net (code "43") (name "/PE4") (class "Default")
      (node (ref "ATMEGA2560") (pin "6") (pinfunction "(OC3B/INT4)PE4_6") (pintype "bidirectional"))
      (node (ref "PORTE") (pin "5") (pinfunction "5_5") (pintype "passive"))
    )
    (net (code "44") (name "/PE5") (class "Default")
      (node (ref "ATMEGA2560") (pin "7") (pinfunction "(OC3C/INT5)PE5_7") (pintype "bidirectional"))
      (node (ref "PORTE") (pin "6") (pinfunction "6_6") (pintype "passive"))
    )
    (net (code "45") (name "/PE6") (class "Default")
      (node (ref "ATMEGA2560") (pin "8") (pinfunction "(T3/INT6)PE6_8") (pintype "bidirectional"))
      (node (ref "PORTE") (pin "7") (pinfunction "7_7") (pintype "passive"))
    )
    (net (code "46") (name "/PE7") (class "Default")
      (node (ref "ATMEGA2560") (pin "9") (pinfunction "(CLKO/ICP3/INT7)PE7_9") (pintype "bidirectional"))
      (node (ref "PORTE") (pin "8") (pinfunction "8_8") (pintype "passive"))
    )
    (net (code "47") (name "/PF0_2") (class "Default")
      (node (ref "ATMEGA2560") (pin "95") (pinfunction "(ADC2)PF2_95") (pintype "bidirectional"))
      (node (ref "ATMEGA2560") (pin "97") (pinfunction "(ADC0)PF0_97") (pintype "bidirectional"))
      (node (ref "BQ76925") (pin "17") (pinfunction "VREF_17") (pintype "output"))
      (node (ref "CREF") (pin "1") (pinfunction "1_1") (pintype "passive"))
      (node (ref "PORTF") (pin "1") (pinfunction "1_1") (pintype "passive"))
      (node (ref "PORTF") (pin "3") (pinfunction "3_3") (pintype "passive"))
    )
    (net (code "48") (name "/PF1") (class "Default")
      (node (ref "ATMEGA2560") (pin "96") (pinfunction "(ADC1)PF1_96") (pintype "bidirectional"))
      (node (ref "BQ76925") (pin "15") (pinfunction "VCOUT_15") (pintype "output"))
      (node (ref "COUT") (pin "1") (pinfunction "1_1") (pintype "passive"))
      (node (ref "PORTF") (pin "2") (pinfunction "2_2") (pintype "passive"))
    )
    (net (code "49") (name "/PF3") (class "Default")
      (node (ref "ATMEGA2560") (pin "94") (pinfunction "(ADC3)PF3_94") (pintype "bidirectional"))
      (node (ref "BQ76925") (pin "14") (pinfunction "VIOUT_14") (pintype "output"))
      (node (ref "COUT2") (pin "1") (pinfunction "1_1") (pintype "passive"))
      (node (ref "PORTF") (pin "4") (pinfunction "4_4") (pintype "passive"))
    )
    (net (code "50") (name "/PF4") (class "Default")
      (node (ref "ATMEGA2560") (pin "93") (pinfunction "(ADC4/TCK)PF4_93") (pintype "bidirectional"))
      (node (ref "BQ76925") (pin "13") (pinfunction "ALERT_13") (pintype "output"))
      (node (ref "PORTF") (pin "5") (pinfunction "5_5") (pintype "passive"))
    )
    (net (code "51") (name "/PF5") (class "Default")
      (node (ref "ATMEGA2560") (pin "92") (pinfunction "(ADC5/TMS)PF5_92") (pintype "bidirectional"))
      (node (ref "PORTF") (pin "6") (pinfunction "6_6") (pintype "passive"))
    )
    (net (code "52") (name "/PF6") (class "Default")
      (node (ref "ATMEGA2560") (pin "91") (pinfunction "(ADC6/TDO)PF6_91") (pintype "bidirectional"))
      (node (ref "R_BRB") (pin "1") (pinfunction "1_1") (pintype "passive"))
    )
    (net (code "53") (name "/PF7") (class "Default")
      (node (ref "ATMEGA2560") (pin "90") (pinfunction "(ADC7/TDI)PF7_90") (pintype "bidirectional"))
      (node (ref "R_BRT") (pin "1") (pinfunction "1_1") (pintype "passive"))
    )
    (net (code "54") (name "/PG0") (class "Default")
      (node (ref "ATMEGA2560") (pin "51") (pinfunction "(WR)PG0_51") (pintype "bidirectional"))
      (node (ref "PORTG") (pin "1") (pinfunction "1_1") (pintype "passive"))
    )
    (net (code "55") (name "/PG1") (class "Default")
      (node (ref "ATMEGA2560") (pin "52") (pinfunction "(RD)PG1_52") (pintype "bidirectional"))
      (node (ref "PORTG") (pin "2") (pinfunction "2_2") (pintype "passive"))
    )
    (net (code "56") (name "/PG2") (class "Default")
      (node (ref "ATMEGA2560") (pin "70") (pinfunction "(ALE)PG2_70") (pintype "bidirectional"))
      (node (ref "PORTG") (pin "3") (pinfunction "3_3") (pintype "passive"))
    )
    (net (code "57") (name "/PG3") (class "Default")
      (node (ref "ATMEGA2560") (pin "28") (pinfunction "(TOSC2)PG3_28") (pintype "bidirectional"))
      (node (ref "PORTG") (pin "4") (pinfunction "4_4") (pintype "passive"))
    )
    (net (code "58") (name "/PG4") (class "Default")
      (node (ref "ATMEGA2560") (pin "29") (pinfunction "(TOSC1)PG4_29") (pintype "bidirectional"))
      (node (ref "PORTG") (pin "5") (pinfunction "5_5") (pintype "passive"))
    )
    (net (code "59") (name "/PG5") (class "Default")
      (node (ref "ATMEGA2560") (pin "1") (pinfunction "(OC0B)PG5_1") (pintype "bidirectional"))
      (node (ref "BUZZ") (pin "-") (pinfunction "2_-") (pintype "passive"))
      (node (ref "PORTG") (pin "6") (pinfunction "6_6") (pintype "passive"))
    )
    (net (code "60") (name "/PH0") (class "Default")
      (node (ref "ATMEGA2560") (pin "12") (pinfunction "PH0(RXD2)_12") (pintype "bidirectional"))
      (node (ref "PORTH") (pin "1") (pinfunction "1_1") (pintype "passive"))
    )
    (net (code "61") (name "/PH1") (class "Default")
      (node (ref "ATMEGA2560") (pin "13") (pinfunction "PH1(TXD2)_13") (pintype "bidirectional"))
      (node (ref "PORTH") (pin "2") (pinfunction "2_2") (pintype "passive"))
    )
    (net (code "62") (name "/PH2") (class "Default")
      (node (ref "ATMEGA2560") (pin "14") (pinfunction "PH2(XCK2)_14") (pintype "bidirectional"))
      (node (ref "PORTH") (pin "3") (pinfunction "3_3") (pintype "passive"))
    )
    (net (code "63") (name "/PH3") (class "Default")
      (node (ref "ATMEGA2560") (pin "15") (pinfunction "PH3(OC4A)_15") (pintype "bidirectional"))
      (node (ref "ESC_BL") (pin "1") (pinfunction "1_1") (pintype "passive"))
      (node (ref "PORTH") (pin "4") (pinfunction "4_4") (pintype "passive"))
    )
    (net (code "64") (name "/PH4") (class "Default")
      (node (ref "ATMEGA2560") (pin "16") (pinfunction "PH4(OC4B)_16") (pintype "bidirectional"))
      (node (ref "ESC_FL") (pin "1") (pinfunction "1_1") (pintype "passive"))
      (node (ref "PORTH") (pin "5") (pinfunction "5_5") (pintype "passive"))
    )
    (net (code "65") (name "/PH5") (class "Default")
      (node (ref "ATMEGA2560") (pin "17") (pinfunction "PH5(OC4C)_17") (pintype "bidirectional"))
      (node (ref "PORTH") (pin "6") (pinfunction "6_6") (pintype "passive"))
    )
    (net (code "66") (name "/PH6") (class "Default")
      (node (ref "ATMEGA2560") (pin "18") (pinfunction "PH6(OC2B)_18") (pintype "bidirectional"))
      (node (ref "PORTH") (pin "7") (pinfunction "7_7") (pintype "passive"))
    )
    (net (code "67") (name "/PH7") (class "Default")
      (node (ref "ATMEGA2560") (pin "27") (pinfunction "PH7(T4)_27") (pintype "bidirectional"))
      (node (ref "PORTH") (pin "8") (pinfunction "8_8") (pintype "passive"))
    )
    (net (code "68") (name "/PJ6") (class "Default")
      (node (ref "ATMEGA2560") (pin "69") (pinfunction "PJ6(PCINT15)_69") (pintype "bidirectional"))
      (node (ref "R_FLB") (pin "1") (pinfunction "1_1") (pintype "passive"))
    )
    (net (code "69") (name "/PJ7") (class "Default")
      (node (ref "ATMEGA2560") (pin "79") (pinfunction "PJ7_79") (pintype "bidirectional"))
      (node (ref "R_FLT") (pin "1") (pinfunction "1_1") (pintype "passive"))
    )
    (net (code "70") (name "/PK0") (class "Default")
      (node (ref "ATMEGA2560") (pin "89") (pinfunction "PK0(ADC8/PCINT16)_89") (pintype "bidirectional"))
      (node (ref "R_BLT") (pin "1") (pinfunction "1_1") (pintype "passive"))
    )
    (net (code "71") (name "/PK1") (class "Default")
      (node (ref "ATMEGA2560") (pin "88") (pinfunction "PK1(ADC9/PCINT17)_88") (pintype "bidirectional"))
      (node (ref "R_BLB") (pin "1") (pinfunction "1_1") (pintype "passive"))
    )
    (net (code "72") (name "/PK2") (class "Default")
      (node (ref "ATMEGA2560") (pin "87") (pinfunction "PK2(ADC10/PCINT18)_87") (pintype "bidirectional"))
      (node (ref "PORTK") (pin "3") (pinfunction "3_3") (pintype "passive"))
    )
    (net (code "73") (name "/PK3") (class "Default")
      (node (ref "ATMEGA2560") (pin "86") (pinfunction "PK3(ADC11/PCINT19)_86") (pintype "bidirectional"))
      (node (ref "PORTK") (pin "4") (pinfunction "4_4") (pintype "passive"))
    )
    (net (code "74") (name "/PK4") (class "Default")
      (node (ref "ATMEGA2560") (pin "85") (pinfunction "PK4(ADC12/PCINT20)_85") (pintype "bidirectional"))
      (node (ref "PORTK") (pin "5") (pinfunction "5_5") (pintype "passive"))
    )
    (net (code "75") (name "/PK5") (class "Default")
      (node (ref "ATMEGA2560") (pin "84") (pinfunction "PK5(ADC13/PCINT21)_84") (pintype "bidirectional"))
      (node (ref "PORTK") (pin "6") (pinfunction "6_6") (pintype "passive"))
    )
    (net (code "76") (name "/PK6") (class "Default")
      (node (ref "ATMEGA2560") (pin "83") (pinfunction "PK6(ADC14/PCINT22)_83") (pintype "bidirectional"))
      (node (ref "PORTK") (pin "7") (pinfunction "7_7") (pintype "passive"))
    )
    (net (code "77") (name "/PK7") (class "Default")
      (node (ref "ATMEGA2560") (pin "82") (pinfunction "PK7(ADC15/PCINT23)_82") (pintype "bidirectional"))
      (node (ref "PORTK") (pin "8") (pinfunction "8_8") (pintype "passive"))
    )
    (net (code "78") (name "/PL0") (class "Default")
      (node (ref "ATMEGA2560") (pin "35") (pinfunction "PL0(ICP4)_35") (pintype "bidirectional"))
      (node (ref "PORTL") (pin "1") (pinfunction "1_1") (pintype "passive"))
    )
    (net (code "79") (name "/PL1") (class "Default")
      (node (ref "ATMEGA2560") (pin "36") (pinfunction "PL1(ICP5)_36") (pintype "bidirectional"))
      (node (ref "PORTL") (pin "2") (pinfunction "2_2") (pintype "passive"))
    )
    (net (code "80") (name "/PL2") (class "Default")
      (node (ref "ATMEGA2560") (pin "37") (pinfunction "PL2(T5)_37") (pintype "bidirectional"))
      (node (ref "PORTL") (pin "3") (pinfunction "3_3") (pintype "passive"))
    )
    (net (code "81") (name "/PL3") (class "Default")
      (node (ref "ATMEGA2560") (pin "38") (pinfunction "PL3(OC5A)_38") (pintype "bidirectional"))
      (node (ref "ESC_FR") (pin "1") (pinfunction "1_1") (pintype "passive"))
      (node (ref "PORTL") (pin "4") (pinfunction "4_4") (pintype "passive"))
    )
    (net (code "82") (name "/PL4") (class "Default")
      (node (ref "ATMEGA2560") (pin "39") (pinfunction "PL4(OC5B)_39") (pintype "bidirectional"))
      (node (ref "ESC_BR") (pin "1") (pinfunction "1_1") (pintype "passive"))
      (node (ref "PORTL") (pin "5") (pinfunction "5_5") (pintype "passive"))
    )
    (net (code "83") (name "/PL5") (class "Default")
      (node (ref "ATMEGA2560") (pin "40") (pinfunction "PL5(OC5C)_40") (pintype "bidirectional"))
      (node (ref "PORTL") (pin "6") (pinfunction "6_6") (pintype "passive"))
    )
    (net (code "84") (name "/PL6") (class "Default")
      (node (ref "ATMEGA2560") (pin "41") (pinfunction "PL6_41") (pintype "bidirectional"))
      (node (ref "PORTL") (pin "7") (pinfunction "7_7") (pintype "passive"))
    )
    (net (code "85") (name "/PL7") (class "Default")
      (node (ref "ATMEGA2560") (pin "42") (pinfunction "PL7_42") (pintype "bidirectional"))
      (node (ref "PORTL") (pin "8") (pinfunction "8_8") (pintype "passive"))
    )
    (net (code "86") (name "/RESET") (class "Default")
      (node (ref "ATMEGA2560") (pin "30") (pinfunction "RESET_30") (pintype "input"))
      (node (ref "C_RES") (pin "1") (pinfunction "1_1") (pintype "passive"))
      (node (ref "D_PD_RES") (pin "C") (pinfunction "C_C") (pintype "passive"))
      (node (ref "D_PU_RES") (pin "A") (pinfunction "A_A") (pintype "passive"))
      (node (ref "RSPI2") (pin "1") (pinfunction "1_1") (pintype "passive"))
      (node (ref "RSPI7") (pin "1") (pinfunction "1_1") (pintype "passive"))
      (node (ref "R_PU_RES") (pin "1") (pinfunction "1_1") (pintype "passive"))
      (node (ref "R_RES") (pin "1") (pinfunction "1_1") (pintype "passive"))
    )
    (net (code "87") (name "/SCK") (class "Default")
      (node (ref "ATMEGA2560") (pin "20") (pinfunction "(SCK/PCINT1)PB1_20") (pintype "bidirectional"))
      (node (ref "PORTB") (pin "2") (pinfunction "2_2") (pintype "passive"))
      (node (ref "RSPI3") (pin "1") (pinfunction "1_1") (pintype "passive"))
      (node (ref "RSPI6") (pin "1") (pinfunction "1_1") (pintype "passive"))
    )
    (net (code "88") (name "/SCL") (class "Default")
      (node (ref "ATMEGA2560") (pin "43") (pinfunction "(SCL/INT0)PD0_43") (pintype "bidirectional"))
      (node (ref "BQ76925") (pin "19") (pinfunction "SCL_19") (pintype "input"))
      (node (ref "I2C") (pin "3") (pinfunction "3_3") (pintype "passive"))
      (node (ref "IMU_BOARD") (pin "3") (pinfunction "3_3") (pintype "passive"))
      (node (ref "PORTD") (pin "1") (pinfunction "1_1") (pintype "passive"))
      (node (ref "RSCL") (pin "2") (pinfunction "2_2") (pintype "passive"))
    )
    (net (code "89") (name "/SDA") (class "Default")
      (node (ref "ATMEGA2560") (pin "44") (pinfunction "(SDA/INT1)PD1_44") (pintype "bidirectional"))
      (node (ref "BQ76925") (pin "18") (pinfunction "SDA_18") (pintype "bidirectional"))
      (node (ref "I2C") (pin "2") (pinfunction "2_2") (pintype "passive"))
      (node (ref "IMU_BOARD") (pin "4") (pinfunction "4_4") (pintype "passive"))
      (node (ref "PORTD") (pin "2") (pinfunction "2_2") (pintype "passive"))
      (node (ref "RSDA") (pin "2") (pinfunction "2_2") (pintype "passive"))
    )
    (net (code "90") (name "/SS") (class "Default")
      (node (ref "ATMEGA2560") (pin "19") (pinfunction "(SS/PCINT0)PB0_19") (pintype "bidirectional"))
      (node (ref "PORTB") (pin "1") (pinfunction "1_1") (pintype "passive"))
      (node (ref "R_PU_SS") (pin "1") (pinfunction "1_1") (pintype "passive"))
    )
    (net (code "91") (name "/VOUT_5085") (class "Default")
      (node (ref "CFF") (pin "1") (pinfunction "1_1") (pintype "passive"))
      (node (ref "COUT1") (pin "1") (pinfunction "+_1") (pintype "passive"))
      (node (ref "C_LP1") (pin "1") (pinfunction "1_1") (pintype "passive"))
      (node (ref "C_LP2") (pin "1") (pinfunction "1_1") (pintype "passive"))
      (node (ref "C_LP3") (pin "1") (pinfunction "1_1") (pintype "passive"))
      (node (ref "C_LP4") (pin "1") (pinfunction "1_1") (pintype "passive"))
      (node (ref "C_LP56") (pin "1") (pinfunction "1_1") (pintype "passive"))
      (node (ref "L2") (pin "P$2") (pinfunction "2_P$2") (pintype "passive"))
      (node (ref "LED_P1") (pin "1") (pinfunction "1_1") (pintype "passive"))
      (node (ref "LED_P1") (pin "3") (pinfunction "3_3") (pintype "passive"))
      (node (ref "LED_P2") (pin "1") (pinfunction "1_1") (pintype "passive"))
      (node (ref "LED_P2") (pin "3") (pinfunction "3_3") (pintype "passive"))
      (node (ref "LED_P3") (pin "1") (pinfunction "1_1") (pintype "passive"))
      (node (ref "LED_P3") (pin "3") (pinfunction "3_3") (pintype "passive"))
      (node (ref "LED_P4") (pin "1") (pinfunction "1_1") (pintype "passive"))
      (node (ref "LED_P4") (pin "3") (pinfunction "3_3") (pintype "passive"))
      (node (ref "LED_P5") (pin "1") (pinfunction "1_1") (pintype "passive"))
      (node (ref "LED_P5") (pin "3") (pinfunction "3_3") (pintype "passive"))
      (node (ref "LED_P6") (pin "1") (pinfunction "1_1") (pintype "passive"))
      (node (ref "LED_P6") (pin "3") (pinfunction "3_3") (pintype "passive"))
      (node (ref "RFB2") (pin "1") (pinfunction "1_1") (pintype "passive"))
    )
    (net (code "92") (name "GND") (class "Default")
      (node (ref "ATMEGA2560") (pin "11") (pinfunction "GND_11") (pintype "power_in"))
      (node (ref "ATMEGA2560") (pin "32") (pinfunction "GND1_32") (pintype "power_in"))
      (node (ref "ATMEGA2560") (pin "62") (pinfunction "GND2_62") (pintype "power_in"))
      (node (ref "ATMEGA2560") (pin "81") (pinfunction "GND3_81") (pintype "power_in"))
      (node (ref "ATMEGA2560") (pin "99") (pinfunction "AGND_99") (pintype "power_in"))
      (node (ref "BAT-MONIT") (pin "P$1") (pinfunction "P$1_P$1") (pintype "bidirectional"))
      (node (ref "BQ76925") (pin "10") (pinfunction "VSS_10") (pintype "power_in"))
      (node (ref "BUTT_RESET") (pin "3") (pinfunction "2_3") (pintype "passive"))
      (node (ref "BUTT_RESET") (pin "4") (pinfunction "2_4") (pintype "passive"))
      (node (ref "BUZZ") (pin "+") (pinfunction "1_+") (pintype "passive"))
      (node (ref "CBAT") (pin "2") (pinfunction "2_2") (pintype "passive"))
      (node (ref "CIN") (pin "2") (pinfunction "2_2") (pintype "passive"))
      (node (ref "CIN1") (pin "2") (pinfunction "2_2") (pintype "passive"))
      (node (ref "CIN2") (pin "2") (pinfunction "2_2") (pintype "passive"))
      (node (ref "CIN3") (pin "2") (pinfunction "2_2") (pintype "passive"))
      (node (ref "CIN4") (pin "2") (pinfunction "2_2") (pintype "passive"))
      (node (ref "CIN5") (pin "2") (pinfunction "2_2") (pintype "passive"))
      (node (ref "CIN6") (pin "2") (pinfunction "2_2") (pintype "passive"))
      (node (ref "CIN_1") (pin "2") (pinfunction "2_2") (pintype "passive"))
      (node (ref "CIN_2") (pin "2") (pinfunction "2_2") (pintype "passive"))
      (node (ref "CI_78") (pin "2") (pinfunction "2_2") (pintype "passive"))
      (node (ref "COUT") (pin "2") (pinfunction "2_2") (pintype "passive"))
      (node (ref "COUT1") (pin "2") (pinfunction "-_2") (pintype "passive"))
      (node (ref "COUT2") (pin "2") (pinfunction "2_2") (pintype "passive"))
      (node (ref "CO_78") (pin "2") (pinfunction "2_2") (pintype "passive"))
      (node (ref "CREF") (pin "2") (pinfunction "2_2") (pintype "passive"))
      (node (ref "CV3P3") (pin "2") (pinfunction "2_2") (pintype "passive"))
      (node (ref "C_AREF") (pin "2") (pinfunction "2_2") (pintype "passive"))
      (node (ref "C_AVCC") (pin "2") (pinfunction "2_2") (pintype "passive"))
      (node (ref "C_CRY1") (pin "1") (pinfunction "1_1") (pintype "passive"))
      (node (ref "C_CRY2") (pin "1") (pinfunction "1_1") (pintype "passive"))
      (node (ref "C_DECO1") (pin "2") (pinfunction "2_2") (pintype "passive"))
      (node (ref "C_DECO2") (pin "2") (pinfunction "2_2") (pintype "passive"))
      (node (ref "C_DECO3") (pin "2") (pinfunction "2_2") (pintype "passive"))
      (node (ref "C_DECO4") (pin "2") (pinfunction "2_2") (pintype "passive"))
      (node (ref "C_LP1") (pin "2") (pinfunction "2_2") (pintype "passive"))
      (node (ref "C_LP2") (pin "2") (pinfunction "2_2") (pintype "passive"))
      (node (ref "C_LP3") (pin "2") (pinfunction "2_2") (pintype "passive"))
      (node (ref "C_LP4") (pin "2") (pinfunction "2_2") (pintype "passive"))
      (node (ref "C_LP56") (pin "2") (pinfunction "2_2") (pintype "passive"))
      (node (ref "C_RES") (pin "2") (pinfunction "2_2") (pintype "passive"))
      (node (ref "D1") (pin "1") (pinfunction "A_2_1") (pintype "passive"))
      (node (ref "D_PD_RES") (pin "A") (pinfunction "A_A") (pintype "passive"))
      (node (ref "ESC-1") (pin "1") (pinfunction "P_1") (pintype "passive"))
      (node (ref "ESC-2") (pin "1") (pinfunction "P_1") (pintype "passive"))
      (node (ref "ESC-3") (pin "1") (pinfunction "P_1") (pintype "passive"))
      (node (ref "ESC-4") (pin "1") (pinfunction "P_1") (pintype "passive"))
      (node (ref "ESC_BL") (pin "2") (pinfunction "2_2") (pintype "passive"))
      (node (ref "ESC_BR") (pin "2") (pinfunction "2_2") (pintype "passive"))
      (node (ref "ESC_FL") (pin "2") (pinfunction "2_2") (pintype "passive"))
      (node (ref "ESC_FR") (pin "2") (pinfunction "2_2") (pintype "passive"))
      (node (ref "H4") (pin "B3,0") (pinfunction "MOUNT_B3,0") (pintype "passive"))
      (node (ref "I2C") (pin "4") (pinfunction "4_4") (pintype "passive"))
      (node (ref "IMU_BOARD") (pin "5") (pinfunction "5_5") (pintype "passive"))
      (node (ref "INV") (pin "3") (pinfunction "GND_3") (pintype "bidirectional"))
      (node (ref "LED_P1") (pin "2") (pinfunction "2_2") (pintype "passive"))
      (node (ref "LED_P1") (pin "4") (pinfunction "4_4") (pintype "passive"))
      (node (ref "LED_P2") (pin "2") (pinfunction "2_2") (pintype "passive"))
      (node (ref "LED_P2") (pin "4") (pinfunction "4_4") (pintype "passive"))
      (node (ref "LED_P3") (pin "2") (pinfunction "2_2") (pintype "passive"))
      (node (ref "LED_P3") (pin "4") (pinfunction "4_4") (pintype "passive"))
      (node (ref "LED_P4") (pin "2") (pinfunction "2_2") (pintype "passive"))
      (node (ref "LED_P4") (pin "4") (pinfunction "4_4") (pintype "passive"))
      (node (ref "LED_P5") (pin "2") (pinfunction "2_2") (pintype "passive"))
      (node (ref "LED_P5") (pin "4") (pinfunction "4_4") (pintype "passive"))
      (node (ref "LED_P6") (pin "2") (pinfunction "2_2") (pintype "passive"))
      (node (ref "LED_P6") (pin "4") (pinfunction "4_4") (pintype "passive"))
      (node (ref "LM5085") (pin "4") (pinfunction "GND_2_4") (pintype "passive"))
      (node (ref "LM5085") (pin "9") (pinfunction "GND_2_9") (pintype "passive"))
      (node (ref "LM7805") (pin "2") (pinfunction "GND_2") (pintype "bidirectional"))
      (node (ref "LM7805") (pin "4") (pinfunction "GND_4") (pintype "bidirectional"))
      (node (ref "PORTA") (pin "9") (pinfunction "9_9") (pintype "passive"))
      (node (ref "PORTB") (pin "9") (pinfunction "9_9") (pintype "passive"))
      (node (ref "PORTD") (pin "9") (pinfunction "9_9") (pintype "passive"))
      (node (ref "PORTE") (pin "9") (pinfunction "9_9") (pintype "passive"))
      (node (ref "PORTF") (pin "9") (pinfunction "9_9") (pintype "passive"))
      (node (ref "PORTG") (pin "7") (pinfunction "7_7") (pintype "passive"))
      (node (ref "PORTG") (pin "9") (pinfunction "9_9") (pintype "passive"))
      (node (ref "PORTH") (pin "9") (pinfunction "9_9") (pintype "passive"))
      (node (ref "PORTJ") (pin "9") (pinfunction "9_9") (pintype "passive"))
      (node (ref "PORTK") (pin "9") (pinfunction "9_9") (pintype "passive"))
      (node (ref "PORTL") (pin "9") (pinfunction "9_9") (pintype "passive"))
      (node (ref "PROGRAMMER10") (pin "10") (pinfunction "10_10") (pintype "passive"))
      (node (ref "PROGRAMMER10") (pin "4") (pinfunction "4_4") (pintype "passive"))
      (node (ref "PROGRAMMER10") (pin "6") (pinfunction "6_6") (pintype "passive"))
      (node (ref "PROGRAMMER10") (pin "8") (pinfunction "8_8") (pintype "passive"))
      (node (ref "PUSH_BUTT") (pin "P$GND") (pinfunction "3_GND_P$GND") (pintype "bidirectional"))
      (node (ref "Q_SEL2") (pin "2") (pinfunction "S_2") (pintype "passive"))
      (node (ref "RADIO_CONTROLLER") (pin "1") (pinfunction "GND_1") (pintype "power_in"))
      (node (ref "RADIO_CONTROLLER") (pin "2") (pinfunction "GND_2") (pintype "power_in"))
      (node (ref "RADIO_CONTROLLER") (pin "3") (pinfunction "GND_3") (pintype "power_in"))
      (node (ref "RADIO_CONTROLLER") (pin "4") (pinfunction "GND_4") (pintype "power_in"))
      (node (ref "RADIO_CONTROLLER") (pin "5") (pinfunction "GND_5") (pintype "power_in"))
      (node (ref "RADIO_CONTROLLER") (pin "6") (pinfunction "GND_6") (pintype "power_in"))
      (node (ref "RADIO_CONTROLLER") (pin "7") (pinfunction "GND_7") (pintype "power_in"))
      (node (ref "RFB1") (pin "2") (pinfunction "2_2") (pintype "passive"))
      (node (ref "RIN") (pin "1") (pinfunction "1_1") (pintype "passive"))
      (node (ref "RLED0") (pin "2") (pinfunction "2_2") (pintype "passive"))
      (node (ref "RLED1") (pin "2") (pinfunction "2_2") (pintype "passive"))
      (node (ref "RLED2") (pin "2") (pinfunction "2_2") (pintype "passive"))
      (node (ref "RLED3") (pin "2") (pinfunction "2_2") (pintype "passive"))
      (node (ref "RLED4") (pin "2") (pinfunction "2_2") (pintype "passive"))
      (node (ref "RLED5") (pin "2") (pinfunction "2_2") (pintype "passive"))
      (node (ref "RLED6") (pin "2") (pinfunction "2_2") (pintype "passive"))
      (node (ref "RLED7") (pin "2") (pinfunction "2_2") (pintype "passive"))
      (node (ref "RSENSE") (pin "1") (pinfunction "1_1") (pintype "passive"))
      (node (ref "RSENSEN") (pin "1") (pinfunction "1_1") (pintype "passive"))
      (node (ref "R_BAT") (pin "2") (pinfunction "2_2") (pintype "passive"))
      (node (ref "R_LCD2") (pin "1") (pinfunction "1_1") (pintype "passive"))
      (node (ref "R_PD_SEL") (pin "1") (pinfunction "1_1") (pintype "passive"))
      (node (ref "R_USB") (pin "2") (pinfunction "2_2") (pintype "passive"))
      (node (ref "R_VCC") (pin "2") (pinfunction "2_2") (pintype "passive"))
      (node (ref "SPI") (pin "6") (pinfunction "6_6") (pintype "bidirectional"))
    )
    (net (code "93") (name "Net-(ATMEGA2560-(A8)PC0)") (class "Default")
      (node (ref "ATMEGA2560") (pin "53") (pinfunction "(A8)PC0_53") (pintype "bidirectional"))
      (node (ref "LED0") (pin "A") (pinfunction "A_A") (pintype "passive"))
    )
    (net (code "94") (name "Net-(ATMEGA2560-(A9)PC1)") (class "Default")
      (node (ref "ATMEGA2560") (pin "54") (pinfunction "(A9)PC1_54") (pintype "bidirectional"))
      (node (ref "LED1") (pin "A") (pinfunction "A_A") (pintype "passive"))
    )
    (net (code "95") (name "Net-(ATMEGA2560-(A10)PC2)") (class "Default")
      (node (ref "ATMEGA2560") (pin "55") (pinfunction "(A10)PC2_55") (pintype "bidirectional"))
      (node (ref "LED2") (pin "A") (pinfunction "A_A") (pintype "passive"))
    )
    (net (code "96") (name "Net-(ATMEGA2560-(A11)PC3)") (class "Default")
      (node (ref "ATMEGA2560") (pin "56") (pinfunction "(A11)PC3_56") (pintype "bidirectional"))
      (node (ref "LED3") (pin "A") (pinfunction "A_A") (pintype "passive"))
    )
    (net (code "97") (name "Net-(ATMEGA2560-(A12)PC4)") (class "Default")
      (node (ref "ATMEGA2560") (pin "57") (pinfunction "(A12)PC4_57") (pintype "bidirectional"))
      (node (ref "LED4") (pin "A") (pinfunction "A_A") (pintype "passive"))
    )
    (net (code "98") (name "Net-(ATMEGA2560-(A13)PC5)") (class "Default")
      (node (ref "ATMEGA2560") (pin "58") (pinfunction "(A13)PC5_58") (pintype "bidirectional"))
      (node (ref "LED5") (pin "A") (pinfunction "A_A") (pintype "passive"))
    )
    (net (code "99") (name "Net-(ATMEGA2560-(A14)PC6)") (class "Default")
      (node (ref "ATMEGA2560") (pin "59") (pinfunction "(A14)PC6_59") (pintype "bidirectional"))
      (node (ref "LED6") (pin "A") (pinfunction "A_A") (pintype "passive"))
    )
    (net (code "100") (name "Net-(ATMEGA2560-(A15)PC7)") (class "Default")
      (node (ref "ATMEGA2560") (pin "60") (pinfunction "(A15)PC7_60") (pintype "bidirectional"))
      (node (ref "LED7") (pin "A") (pinfunction "A_A") (pintype "passive"))
    )
    (net (code "101") (name "Net-(ATMEGA2560-AREF)") (class "Default")
      (node (ref "ATMEGA2560") (pin "98") (pinfunction "AREF_98") (pintype "bidirectional"))
      (node (ref "C_AREF") (pin "1") (pinfunction "1_1") (pintype "passive"))
    )
    (net (code "102") (name "Net-(ATMEGA2560-AVCC)") (class "Default")
      (node (ref "ATMEGA2560") (pin "100") (pinfunction "AVCC_100") (pintype "power_in"))
      (node (ref "C_AVCC") (pin "1") (pinfunction "1_1") (pintype "passive"))
      (node (ref "L1") (pin "2") (pinfunction "2_2") (pintype "passive"))
    )
    (net (code "103") (name "Net-(ATMEGA2560-XTAL1)") (class "Default")
      (node (ref "16MHZ") (pin "1") (pinfunction "1_1") (pintype "passive"))
      (node (ref "ATMEGA2560") (pin "34") (pinfunction "XTAL1_34") (pintype "input"))
      (node (ref "C_CRY1") (pin "2") (pinfunction "2_2") (pintype "passive"))
    )
    (net (code "104") (name "Net-(ATMEGA2560-XTAL2)") (class "Default")
      (node (ref "16MHZ") (pin "2") (pinfunction "2_2") (pintype "passive"))
      (node (ref "ATMEGA2560") (pin "33") (pinfunction "XTAL2_33") (pintype "output"))
      (node (ref "C_CRY2") (pin "2") (pinfunction "2_2") (pintype "passive"))
    )
    (net (code "105") (name "Net-(BAT-MONIT-PadP$2)") (class "Default")
      (node (ref "BAT-MONIT") (pin "P$2") (pinfunction "P$2_P$2") (pintype "bidirectional"))
      (node (ref "RIN1") (pin "1") (pinfunction "1_1") (pintype "passive"))
    )
    (net (code "106") (name "Net-(BAT-MONIT-PadP$3)") (class "Default")
      (node (ref "BAT-MONIT") (pin "P$3") (pinfunction "P$3_P$3") (pintype "bidirectional"))
      (node (ref "RIN2") (pin "1") (pinfunction "1_1") (pintype "passive"))
    )
    (net (code "107") (name "Net-(BAT-MONIT-PadP$4)") (class "Default")
      (node (ref "BAT-MONIT") (pin "P$4") (pinfunction "P$4_P$4") (pintype "bidirectional"))
      (node (ref "JP4") (pin "1") (pinfunction "1_1") (pintype "passive"))
      (node (ref "RIN3") (pin "1") (pinfunction "1_1") (pintype "passive"))
    )
    (net (code "108") (name "Net-(BAT-MONIT-PadP$5)") (class "Default")
      (node (ref "BAT-MONIT") (pin "P$5") (pinfunction "P$5_P$5") (pintype "bidirectional"))
      (node (ref "JP4") (pin "2") (pinfunction "2_2") (pintype "passive"))
      (node (ref "JP5") (pin "1") (pinfunction "1_1") (pintype "passive"))
      (node (ref "RIN4") (pin "1") (pinfunction "1_1") (pintype "passive"))
    )
    (net (code "109") (name "Net-(BAT-MONIT-PadP$6)") (class "Default")
      (node (ref "BAT-MONIT") (pin "P$6") (pinfunction "P$6_P$6") (pintype "bidirectional"))
      (node (ref "JP5") (pin "2") (pinfunction "2_2") (pintype "passive"))
      (node (ref "JP6") (pin "1") (pinfunction "1_1") (pintype "passive"))
      (node (ref "RIN5") (pin "1") (pinfunction "1_1") (pintype "passive"))
    )
    (net (code "110") (name "Net-(BAT-PadC)") (class "Default")
      (node (ref "BAT") (pin "C") (pinfunction "C_C") (pintype "passive"))
      (node (ref "R_BAT") (pin "1") (pinfunction "1_1") (pintype "passive"))
    )
    (net (code "111") (name "Net-(BQ76925-BAT)") (class "Default")
      (node (ref "BQ76925") (pin "1") (pinfunction "VCTL_1") (pintype "output"))
      (node (ref "BQ76925") (pin "2") (pinfunction "BAT_2") (pintype "power_in"))
      (node (ref "CBAT") (pin "1") (pinfunction "1_1") (pintype "passive"))
      (node (ref "RBAT") (pin "2") (pinfunction "2_2") (pintype "passive"))
    )
    (net (code "112") (name "Net-(BQ76925-SENSEN)") (class "Default")
      (node (ref "BQ76925") (pin "11") (pinfunction "SENSEN_11") (pintype "input"))
      (node (ref "CSENSE") (pin "1") (pinfunction "1_1") (pintype "passive"))
      (node (ref "RSENSEN") (pin "2") (pinfunction "2_2") (pintype "passive"))
    )
    (net (code "113") (name "Net-(BQ76925-SENSEP)") (class "Default")
      (node (ref "BQ76925") (pin "12") (pinfunction "SENSEP_12") (pintype "input"))
      (node (ref "CSENSE") (pin "2") (pinfunction "2_2") (pintype "passive"))
      (node (ref "RSENSEP") (pin "2") (pinfunction "2_2") (pintype "passive"))
    )
    (net (code "114") (name "Net-(BQ76925-VC0)") (class "Default")
      (node (ref "BQ76925") (pin "9") (pinfunction "VC0_9") (pintype "input"))
      (node (ref "CIN") (pin "1") (pinfunction "1_1") (pintype "passive"))
      (node (ref "RIN") (pin "2") (pinfunction "2_2") (pintype "passive"))
    )
    (net (code "115") (name "Net-(BQ76925-VC1)") (class "Default")
      (node (ref "BQ76925") (pin "8") (pinfunction "VC1_8") (pintype "input"))
      (node (ref "CIN1") (pin "1") (pinfunction "1_1") (pintype "passive"))
      (node (ref "RIN1") (pin "2") (pinfunction "2_2") (pintype "passive"))
    )
    (net (code "116") (name "Net-(BQ76925-VC2)") (class "Default")
      (node (ref "BQ76925") (pin "7") (pinfunction "VC2_7") (pintype "input"))
      (node (ref "CIN2") (pin "1") (pinfunction "1_1") (pintype "passive"))
      (node (ref "RIN2") (pin "2") (pinfunction "2_2") (pintype "passive"))
    )
    (net (code "117") (name "Net-(BQ76925-VC3)") (class "Default")
      (node (ref "BQ76925") (pin "6") (pinfunction "VC3_6") (pintype "input"))
      (node (ref "CIN3") (pin "1") (pinfunction "1_1") (pintype "passive"))
      (node (ref "RIN3") (pin "2") (pinfunction "2_2") (pintype "passive"))
    )
    (net (code "118") (name "Net-(BQ76925-VC4)") (class "Default")
      (node (ref "BQ76925") (pin "5") (pinfunction "VC4_5") (pintype "input"))
      (node (ref "CIN4") (pin "1") (pinfunction "1_1") (pintype "passive"))
      (node (ref "RIN4") (pin "2") (pinfunction "2_2") (pintype "passive"))
    )
    (net (code "119") (name "Net-(BQ76925-VC5)") (class "Default")
      (node (ref "BQ76925") (pin "4") (pinfunction "VC5_4") (pintype "input"))
      (node (ref "CIN5") (pin "1") (pinfunction "1_1") (pintype "passive"))
      (node (ref "RIN5") (pin "2") (pinfunction "2_2") (pintype "passive"))
    )
    (net (code "120") (name "Net-(BQ76925-VC6)") (class "Default")
      (node (ref "BQ76925") (pin "3") (pinfunction "VC6_3") (pintype "input"))
      (node (ref "CIN6") (pin "1") (pinfunction "1_1") (pintype "passive"))
      (node (ref "RIN6") (pin "2") (pinfunction "2_2") (pintype "passive"))
    )
    (net (code "121") (name "Net-(BUTT_RESET-1-Pad2)") (class "Default")
      (node (ref "BUTT_RESET") (pin "1") (pinfunction "1_1") (pintype "passive"))
      (node (ref "BUTT_RESET") (pin "2") (pinfunction "1_2") (pintype "passive"))
      (node (ref "R_RES") (pin "2") (pinfunction "2_2") (pintype "passive"))
    )
    (net (code "122") (name "Net-(D1-K)") (class "Default")
      (node (ref "D1") (pin "2") (pinfunction "K_2") (pintype "passive"))
      (node (ref "L2") (pin "P$1") (pinfunction "1_P$1") (pintype "passive"))
      (node (ref "M1") (pin "5") (pinfunction "DRAIN_2_5") (pintype "passive"))
      (node (ref "M1") (pin "6") (pinfunction "DRAIN_2_6") (pintype "passive"))
      (node (ref "M1") (pin "7") (pinfunction "DRAIN_2_7") (pintype "passive"))
      (node (ref "M1") (pin "8") (pinfunction "DRAIN_2_8") (pintype "passive"))
      (node (ref "M1") (pin "9") (pinfunction "DRAIN_2_9") (pintype "passive"))
    )
    (net (code "123") (name "Net-(INV-Y)") (class "Default")
      (node (ref "INV") (pin "4") (pinfunction "Y_4") (pintype "bidirectional"))
      (node (ref "Q_SEL2") (pin "1") (pinfunction "G_1") (pintype "passive"))
      (node (ref "R_PD_SEL") (pin "2") (pinfunction "2_2") (pintype "passive"))
    )
    (net (code "124") (name "Net-(LED0-PadC)") (class "Default")
      (node (ref "LED0") (pin "C") (pinfunction "C_C") (pintype "passive"))
      (node (ref "RLED0") (pin "1") (pinfunction "1_1") (pintype "passive"))
    )
    (net (code "125") (name "Net-(LED1-PadC)") (class "Default")
      (node (ref "LED1") (pin "C") (pinfunction "C_C") (pintype "passive"))
      (node (ref "RLED1") (pin "1") (pinfunction "1_1") (pintype "passive"))
    )
    (net (code "126") (name "Net-(LED2-PadC)") (class "Default")
      (node (ref "LED2") (pin "C") (pinfunction "C_C") (pintype "passive"))
      (node (ref "RLED2") (pin "1") (pinfunction "1_1") (pintype "passive"))
    )
    (net (code "127") (name "Net-(LED3-PadC)") (class "Default")
      (node (ref "LED3") (pin "C") (pinfunction "C_C") (pintype "passive"))
      (node (ref "RLED3") (pin "1") (pinfunction "1_1") (pintype "passive"))
    )
    (net (code "128") (name "Net-(LED4-PadC)") (class "Default")
      (node (ref "LED4") (pin "C") (pinfunction "C_C") (pintype "passive"))
      (node (ref "RLED4") (pin "1") (pinfunction "1_1") (pintype "passive"))
    )
    (net (code "129") (name "Net-(LED5-PadC)") (class "Default")
      (node (ref "LED5") (pin "C") (pinfunction "C_C") (pintype "passive"))
      (node (ref "RLED5") (pin "1") (pinfunction "1_1") (pintype "passive"))
    )
    (net (code "130") (name "Net-(LED6-PadC)") (class "Default")
      (node (ref "LED6") (pin "C") (pinfunction "C_C") (pintype "passive"))
      (node (ref "RLED6") (pin "1") (pinfunction "1_1") (pintype "passive"))
    )
    (net (code "131") (name "Net-(LED7-PadC)") (class "Default")
      (node (ref "LED7") (pin "C") (pinfunction "C_C") (pintype "passive"))
      (node (ref "RLED7") (pin "1") (pinfunction "1_1") (pintype "passive"))
    )
    (net (code "132") (name "Net-(LM5085-ADJ)") (class "Default")
      (node (ref "CADJ") (pin "2") (pinfunction "2_2") (pintype "passive"))
      (node (ref "LM5085") (pin "1") (pinfunction "ADJ_1") (pintype "passive"))
      (node (ref "RADJ") (pin "2") (pinfunction "2_2") (pintype "passive"))
    )
    (net (code "133") (name "Net-(LM5085-FB)") (class "Default")
      (node (ref "CFF") (pin "2") (pinfunction "2_2") (pintype "passive"))
      (node (ref "LM5085") (pin "3") (pinfunction "FB_3") (pintype "passive"))
      (node (ref "RFB1") (pin "1") (pinfunction "1_1") (pintype "passive"))
      (node (ref "RFB2") (pin "2") (pinfunction "2_2") (pintype "passive"))
    )
    (net (code "134") (name "Net-(LM5085-ISEN)") (class "Default")
      (node (ref "LM5085") (pin "5") (pinfunction "ISEN_5") (pintype "passive"))
      (node (ref "M1") (pin "1") (pinfunction "SOURCE_2_1") (pintype "passive"))
      (node (ref "M1") (pin "2") (pinfunction "SOURCE_2_2") (pintype "passive"))
      (node (ref "M1") (pin "3") (pinfunction "SOURCE_2_3") (pintype "passive"))
      (node (ref "RSNS") (pin "2") (pinfunction "2_2") (pintype "passive"))
    )
    (net (code "135") (name "Net-(LM5085-PGATE)") (class "Default")
      (node (ref "LM5085") (pin "6") (pinfunction "PGATE_6") (pintype "passive"))
      (node (ref "M1") (pin "4") (pinfunction "GATE_4") (pintype "passive"))
    )
    (net (code "136") (name "Net-(LM5085-RT)") (class "Default")
      (node (ref "LM5085") (pin "2") (pinfunction "RT_2") (pintype "passive"))
      (node (ref "RT") (pin "2") (pinfunction "2_2") (pintype "passive"))
    )
    (net (code "137") (name "Net-(LM5085-VCC)") (class "Default")
      (node (ref "CVCC") (pin "2") (pinfunction "2_2") (pintype "passive"))
      (node (ref "LM5085") (pin "7") (pinfunction "VCC_7") (pintype "passive"))
    )
    (net (code "138") (name "Net-(LM7805-IN)") (class "Default")
      (node (ref "CI_78") (pin "1") (pinfunction "1_1") (pintype "passive"))
      (node (ref "LM7805") (pin "1") (pinfunction "IN_1") (pintype "bidirectional"))
      (node (ref "Q_SEL1") (pin "2") (pinfunction "S_2") (pintype "passive"))
    )
    (net (code "139") (name "Net-(PROGRAMMER10-Pad1)") (class "Default")
      (node (ref "PROGRAMMER10") (pin "1") (pinfunction "1_1") (pintype "passive"))
      (node (ref "RSPI1") (pin "2") (pinfunction "2_2") (pintype "passive"))
    )
    (net (code "140") (name "Net-(PROGRAMMER10-Pad5)") (class "Default")
      (node (ref "PROGRAMMER10") (pin "5") (pinfunction "5_5") (pintype "passive"))
      (node (ref "RSPI2") (pin "2") (pinfunction "2_2") (pintype "passive"))
    )
    (net (code "141") (name "Net-(PROGRAMMER10-Pad7)") (class "Default")
      (node (ref "PROGRAMMER10") (pin "7") (pinfunction "7_7") (pintype "passive"))
      (node (ref "RSPI3") (pin "2") (pinfunction "2_2") (pintype "passive"))
    )
    (net (code "142") (name "Net-(PROGRAMMER10-Pad9)") (class "Default")
      (node (ref "PROGRAMMER10") (pin "9") (pinfunction "9_9") (pintype "passive"))
      (node (ref "RSPI4") (pin "2") (pinfunction "2_2") (pintype "passive"))
    )
    (net (code "143") (name "Net-(Q_SEL1-G)") (class "Default")
      (node (ref "Q_SEL1") (pin "1") (pinfunction "G_1") (pintype "passive"))
      (node (ref "Q_SEL2") (pin "3") (pinfunction "D_3") (pintype "passive"))
      (node (ref "R_PU_SEL") (pin "1") (pinfunction "1_1") (pintype "passive"))
    )
    (net (code "144") (name "Net-(RSPI5-Pad2)") (class "Default")
      (node (ref "RSPI5") (pin "2") (pinfunction "2_2") (pintype "passive"))
      (node (ref "SPI") (pin "1") (pinfunction "1_1") (pintype "bidirectional"))
    )
    (net (code "145") (name "Net-(RSPI6-Pad2)") (class "Default")
      (node (ref "RSPI6") (pin "2") (pinfunction "2_2") (pintype "passive"))
      (node (ref "SPI") (pin "3") (pinfunction "3_3") (pintype "bidirectional"))
    )
    (net (code "146") (name "Net-(RSPI7-Pad2)") (class "Default")
      (node (ref "RSPI7") (pin "2") (pinfunction "2_2") (pintype "passive"))
      (node (ref "SPI") (pin "5") (pinfunction "5_5") (pintype "bidirectional"))
    )
    (net (code "147") (name "Net-(RSPI8-Pad2)") (class "Default")
      (node (ref "RSPI8") (pin "2") (pinfunction "2_2") (pintype "passive"))
      (node (ref "SPI") (pin "4") (pinfunction "4_4") (pintype "bidirectional"))
    )
    (net (code "148") (name "Net-(R_USB-Pad1)") (class "Default")
      (node (ref "R_USB") (pin "1") (pinfunction "1_1") (pintype "passive"))
      (node (ref "USB") (pin "C") (pinfunction "C_C") (pintype "passive"))
    )
    (net (code "149") (name "Net-(R_VCC-Pad1)") (class "Default")
      (node (ref "R_VCC") (pin "1") (pinfunction "1_1") (pintype "passive"))
      (node (ref "VCC") (pin "C") (pinfunction "C_C") (pintype "passive"))
    )
    (net (code "150") (name "VCC") (class "Default")
      (node (ref "ATMEGA2560") (pin "10") (pinfunction "VCC_10") (pintype "power_in"))
      (node (ref "ATMEGA2560") (pin "31") (pinfunction "VCC1_31") (pintype "power_in"))
      (node (ref "ATMEGA2560") (pin "61") (pinfunction "VCC2_61") (pintype "power_in"))
      (node (ref "ATMEGA2560") (pin "80") (pinfunction "VCC3_80") (pintype "power_in"))
      (node (ref "CO_78") (pin "1") (pinfunction "1_1") (pintype "passive"))
      (node (ref "C_DECO1") (pin "1") (pinfunction "1_1") (pintype "passive"))
      (node (ref "C_DECO2") (pin "1") (pinfunction "1_1") (pintype "passive"))
      (node (ref "C_DECO3") (pin "1") (pinfunction "1_1") (pintype "passive"))
      (node (ref "C_DECO4") (pin "1") (pinfunction "1_1") (pintype "passive"))
      (node (ref "D_PU_RES") (pin "C") (pinfunction "C_C") (pintype "passive"))
      (node (ref "D_SEL") (pin "C") (pinfunction "C_C") (pintype "passive"))
      (node (ref "I2C") (pin "1") (pinfunction "1_1") (pintype "passive"))
      (node (ref "IMU_BOARD") (pin "6") (pinfunction "6_6") (pintype "passive"))
      (node (ref "INV") (pin "5") (pinfunction "VCC_5") (pintype "bidirectional"))
      (node (ref "L1") (pin "1") (pinfunction "1_1") (pintype "passive"))
      (node (ref "LM7805") (pin "3") (pinfunction "OUT_3") (pintype "bidirectional"))
      (node (ref "PORTB") (pin "10") (pinfunction "10_10") (pintype "passive"))
      (node (ref "PORTD") (pin "10") (pinfunction "10_10") (pintype "passive"))
      (node (ref "PORTE") (pin "10") (pinfunction "10_10") (pintype "passive"))
      (node (ref "PORTF") (pin "10") (pinfunction "10_10") (pintype "passive"))
      (node (ref "PORTG") (pin "10") (pinfunction "10_10") (pintype "passive"))
      (node (ref "PORTG") (pin "8") (pinfunction "8_8") (pintype "passive"))
      (node (ref "PORTH") (pin "10") (pinfunction "10_10") (pintype "passive"))
      (node (ref "PORTJ") (pin "10") (pinfunction "10_10") (pintype "passive"))
      (node (ref "PORTK") (pin "10") (pinfunction "10_10") (pintype "passive"))
      (node (ref "PORTL") (pin "10") (pinfunction "10_10") (pintype "passive"))
      (node (ref "RADIO_CONTROLLER") (pin "10") (pinfunction "5V_10") (pintype "power_in"))
      (node (ref "RADIO_CONTROLLER") (pin "11") (pinfunction "5V_11") (pintype "power_in"))
      (node (ref "RADIO_CONTROLLER") (pin "12") (pinfunction "5V_12") (pintype "power_in"))
      (node (ref "RADIO_CONTROLLER") (pin "13") (pinfunction "5V_13") (pintype "power_in"))
      (node (ref "RADIO_CONTROLLER") (pin "14") (pinfunction "5V_14") (pintype "power_in"))
      (node (ref "RADIO_CONTROLLER") (pin "8") (pinfunction "5V_8") (pintype "power_in"))
      (node (ref "RADIO_CONTROLLER") (pin "9") (pinfunction "5V_9") (pintype "power_in"))
      (node (ref "RSCL") (pin "1") (pinfunction "1_1") (pintype "passive"))
      (node (ref "RSDA") (pin "1") (pinfunction "1_1") (pintype "passive"))
      (node (ref "R_LCD1") (pin "2") (pinfunction "2_2") (pintype "passive"))
      (node (ref "R_PU_RES") (pin "2") (pinfunction "2_2") (pintype "passive"))
      (node (ref "R_PU_SS") (pin "2") (pinfunction "2_2") (pintype "passive"))
      (node (ref "VCC") (pin "A") (pinfunction "A_A") (pintype "passive"))
    )
    (net (code "151") (name "V_BATT") (class "Default")
      (node (ref "BAT-MONIT") (pin "P$7") (pinfunction "P$7_P$7") (pintype "bidirectional"))
      (node (ref "CADJ") (pin "1") (pinfunction "1_1") (pintype "passive"))
      (node (ref "CIN_1") (pin "1") (pinfunction "1_1") (pintype "passive"))
      (node (ref "CIN_2") (pin "1") (pinfunction "1_1") (pintype "passive"))
      (node (ref "CVCC") (pin "1") (pinfunction "1_1") (pintype "passive"))
      (node (ref "JP6") (pin "2") (pinfunction "2_2") (pintype "passive"))
      (node (ref "LM5085") (pin "8") (pinfunction "VIN_8") (pintype "passive"))
      (node (ref "PUSH_BUTT") (pin "P$LOAD") (pinfunction "2_LOAD_P$LOAD") (pintype "bidirectional"))
      (node (ref "Q_SEL1") (pin "3") (pinfunction "D_3") (pintype "passive"))
      (node (ref "RADJ") (pin "1") (pinfunction "1_1") (pintype "passive"))
      (node (ref "RBAT") (pin "1") (pinfunction "1_1") (pintype "passive"))
      (node (ref "RIN6") (pin "1") (pinfunction "1_1") (pintype "passive"))
      (node (ref "RSNS") (pin "1") (pinfunction "1_1") (pintype "passive"))
      (node (ref "RT") (pin "1") (pinfunction "1_1") (pintype "passive"))
      (node (ref "R_PU_SEL") (pin "2") (pinfunction "2_2") (pintype "passive"))
    )
    (net (code "152") (name "V_USB") (class "Default")
      (node (ref "D_SEL") (pin "A") (pinfunction "A_A") (pintype "passive"))
      (node (ref "INV") (pin "2") (pinfunction "A_2") (pintype "bidirectional"))
      (node (ref "PROGRAMMER10") (pin "2") (pinfunction "2_2") (pintype "passive"))
      (node (ref "SPI") (pin "2") (pinfunction "2_2") (pintype "bidirectional"))
      (node (ref "USB") (pin "A") (pinfunction "A_A") (pintype "passive"))
    )
    (net (code "153") (name "unconnected-(BQ76925-VTB-Pad16)") (class "Default")
      (node (ref "BQ76925") (pin "16") (pinfunction "VTB_16") (pintype "output"))
    )
    (net (code "154") (name "unconnected-(IMU_BOARD-Pad1)") (class "Default")
      (node (ref "IMU_BOARD") (pin "1") (pinfunction "1_1") (pintype "passive"))
    )
    (net (code "155") (name "unconnected-(INV-NC-Pad1)") (class "Default")
      (node (ref "INV") (pin "1") (pinfunction "NC_1") (pintype "bidirectional"))
    )
    (net (code "156") (name "unconnected-(PROGRAMMER10-Pad3)") (class "Default")
      (node (ref "PROGRAMMER10") (pin "3") (pinfunction "3_3") (pintype "passive"))
    )
    (net (code "157") (name "unconnected-(RADIO_CONTROLLER-7-Pad21)") (class "Default")
      (node (ref "RADIO_CONTROLLER") (pin "21") (pinfunction "7_21") (pintype "bidirectional"))
    )
  )
)
